# HDMI_RGB_LVDS_fertig_V5.net
KiCad netlist of a schematic drawn in EAGLE
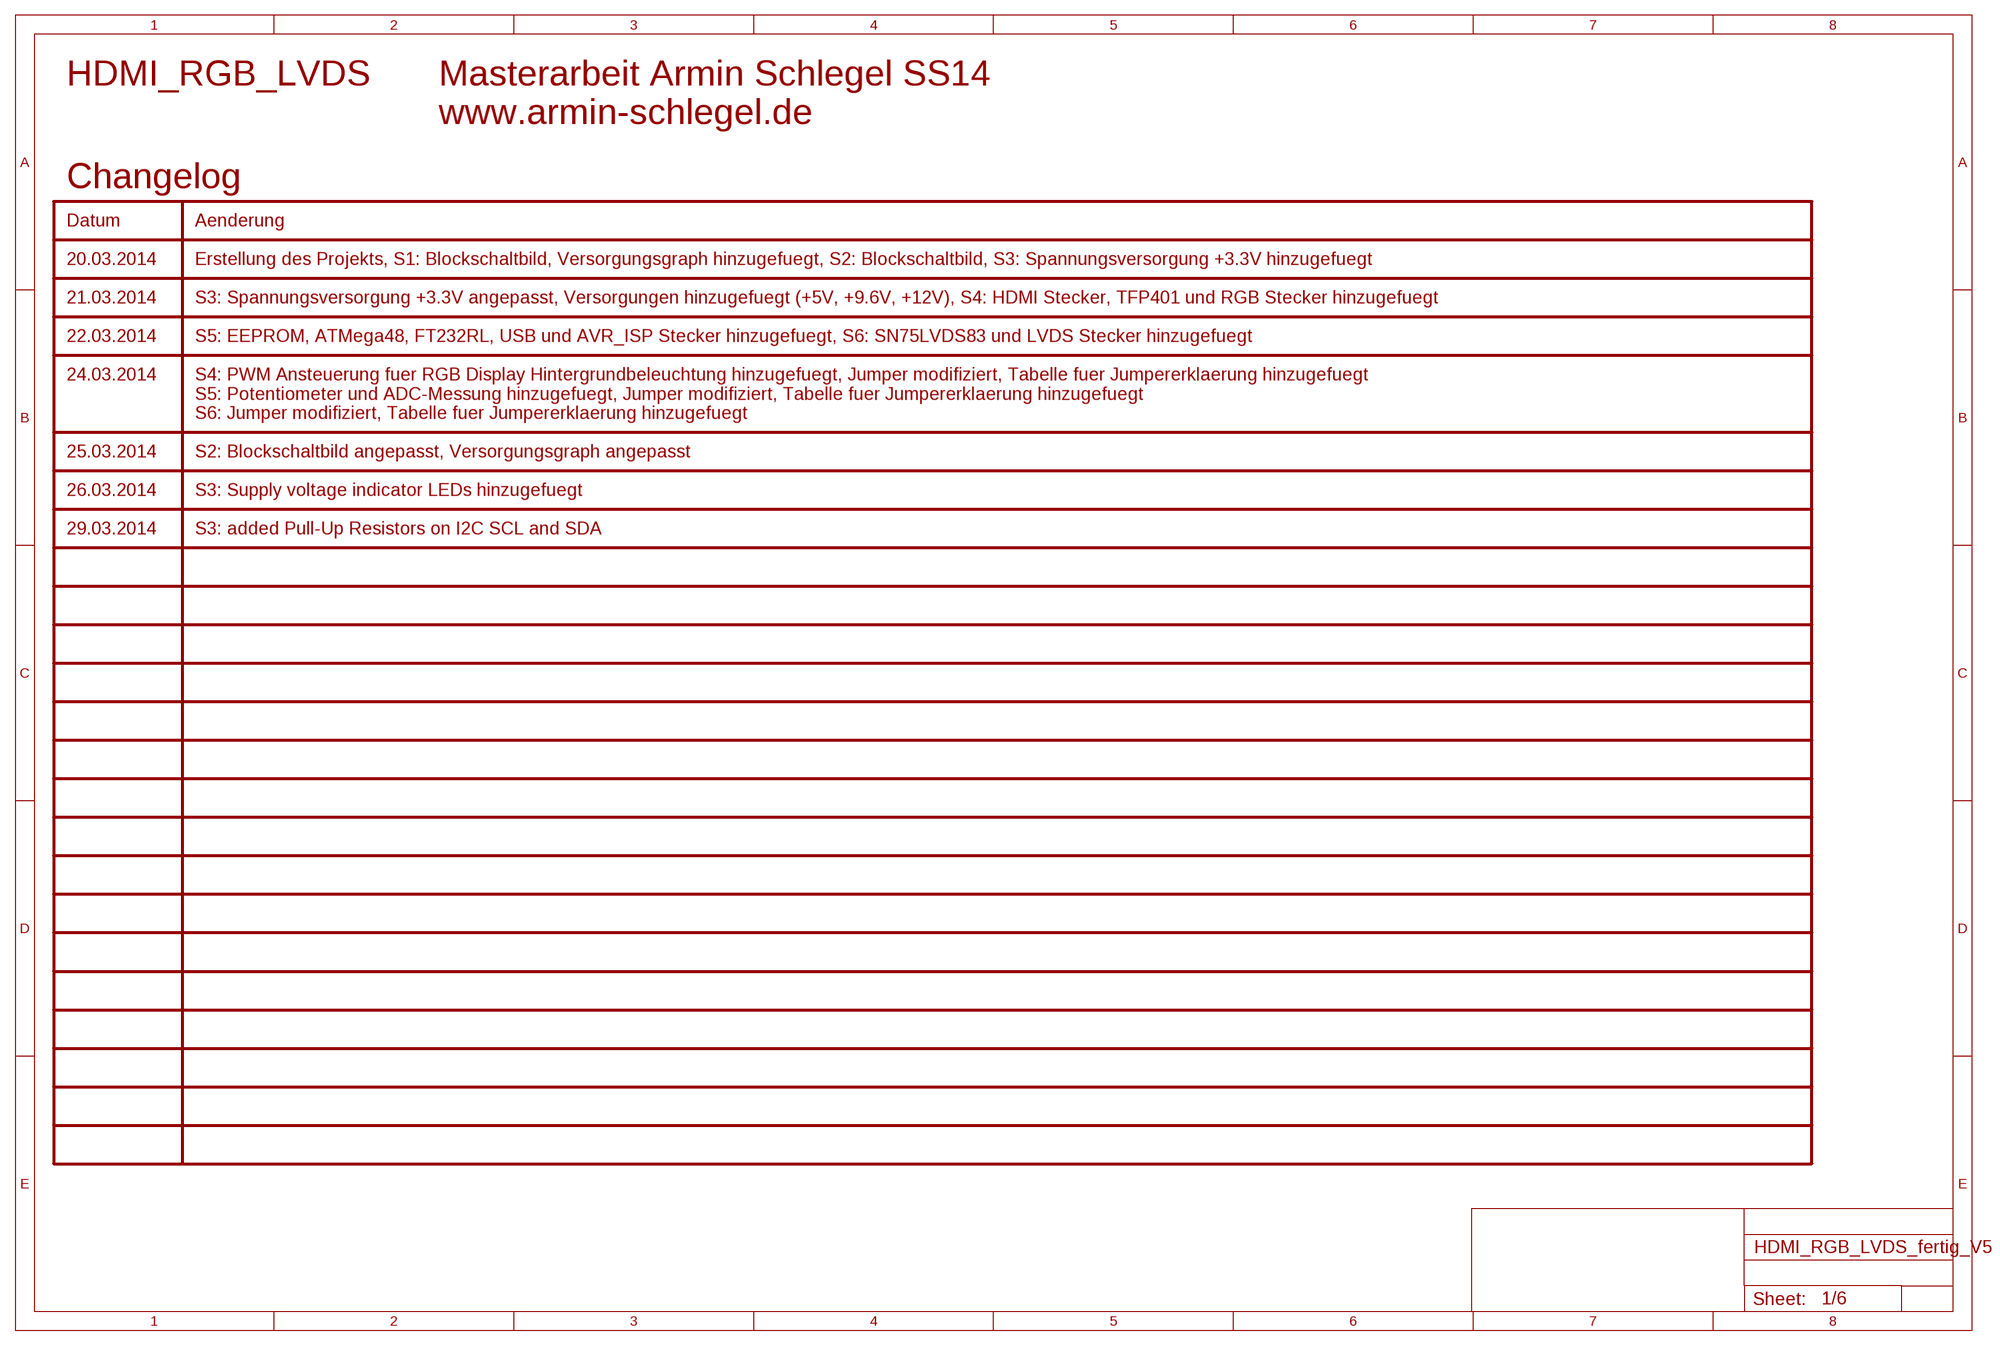
[diagram p0: schematic, sheet 1]
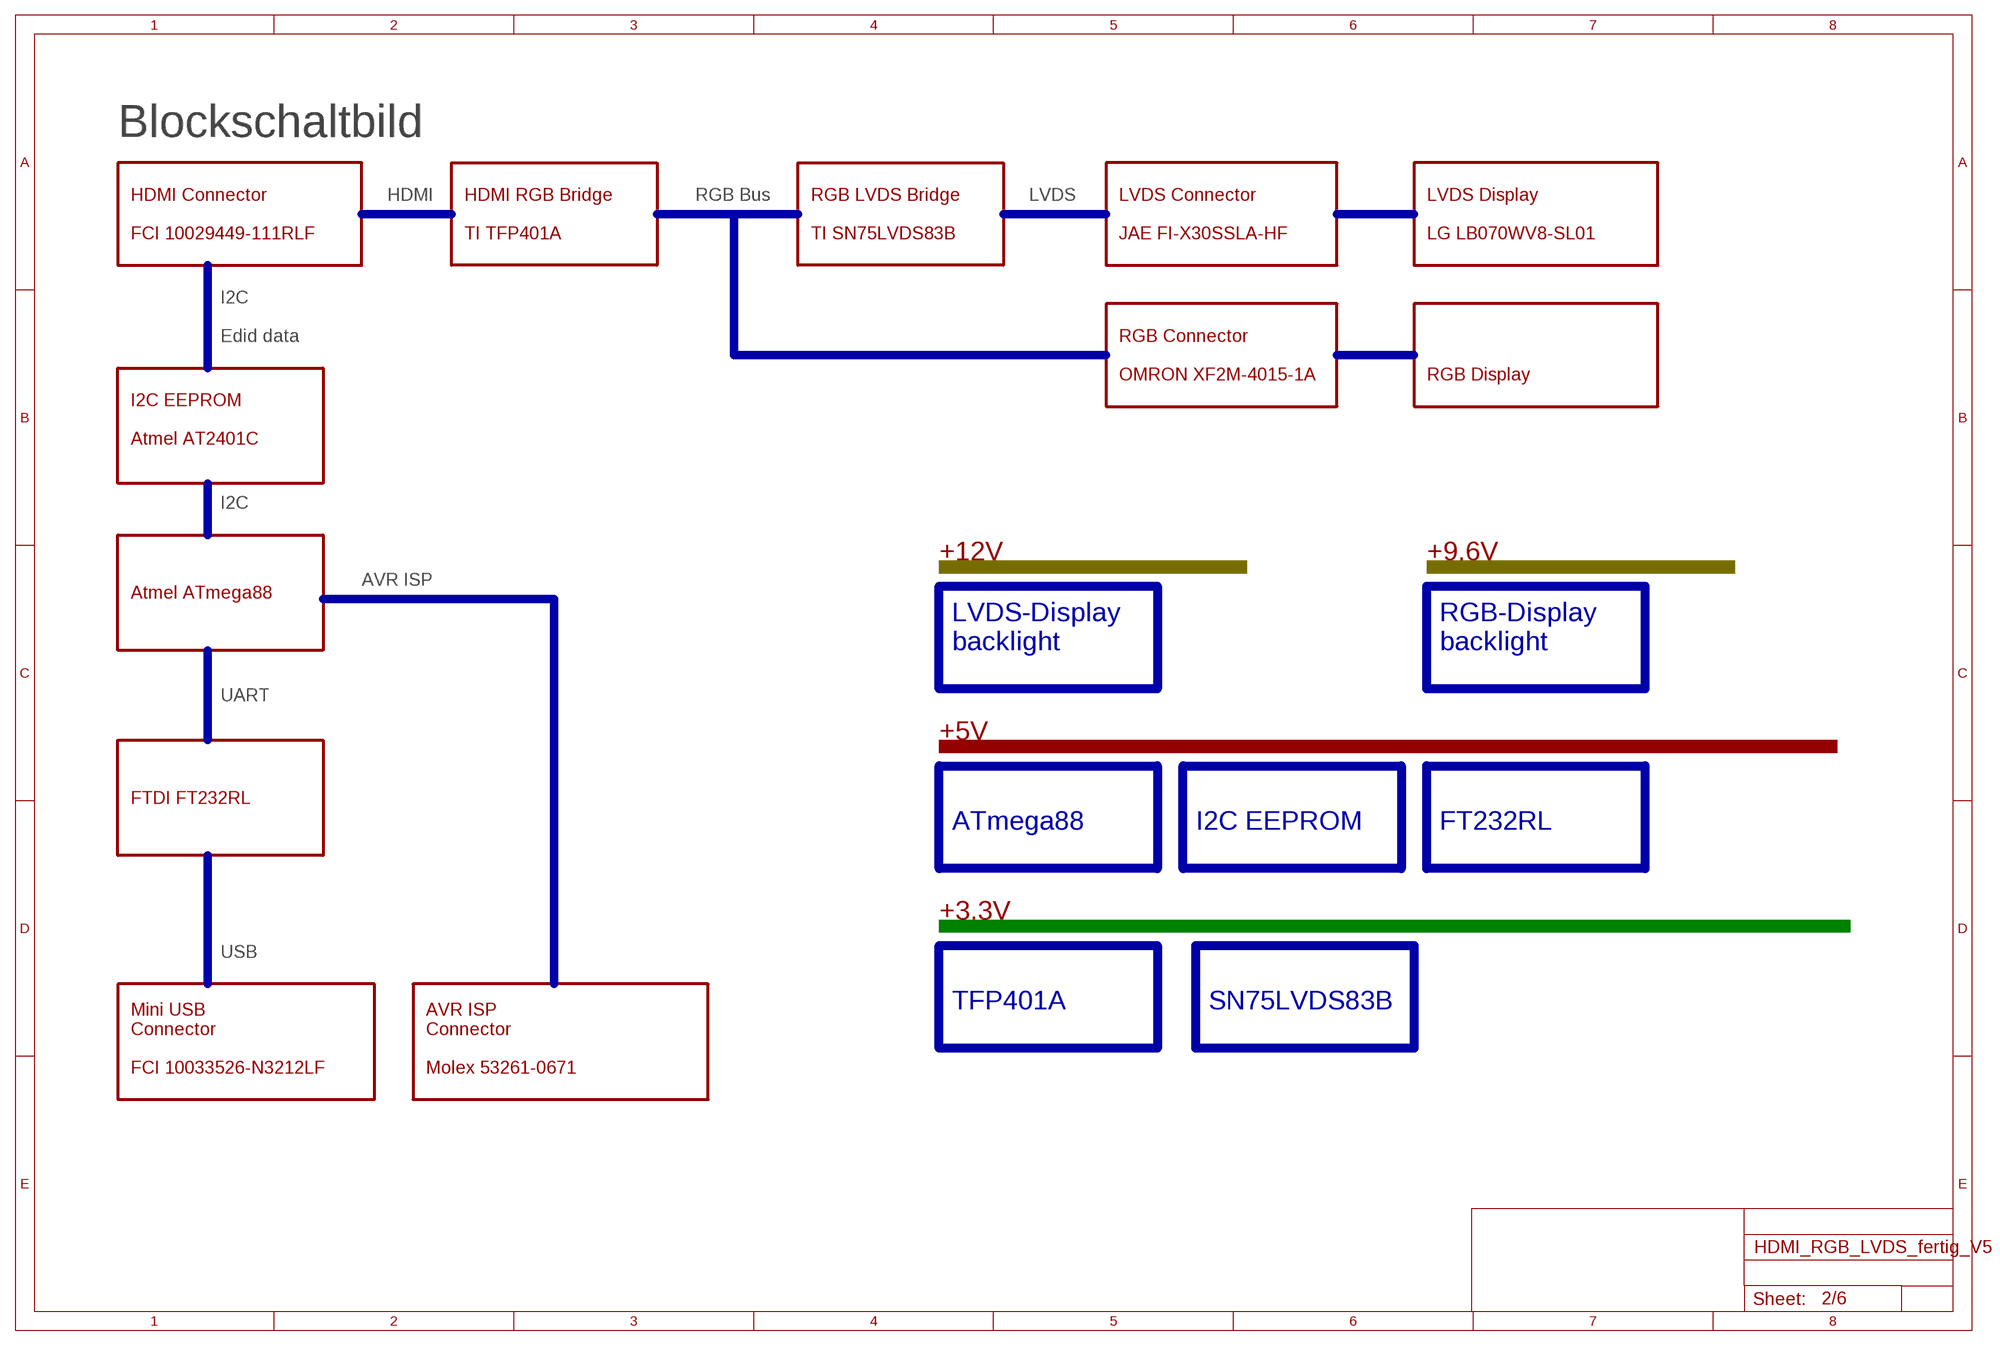
[diagram p1: schematic, sheet 2]
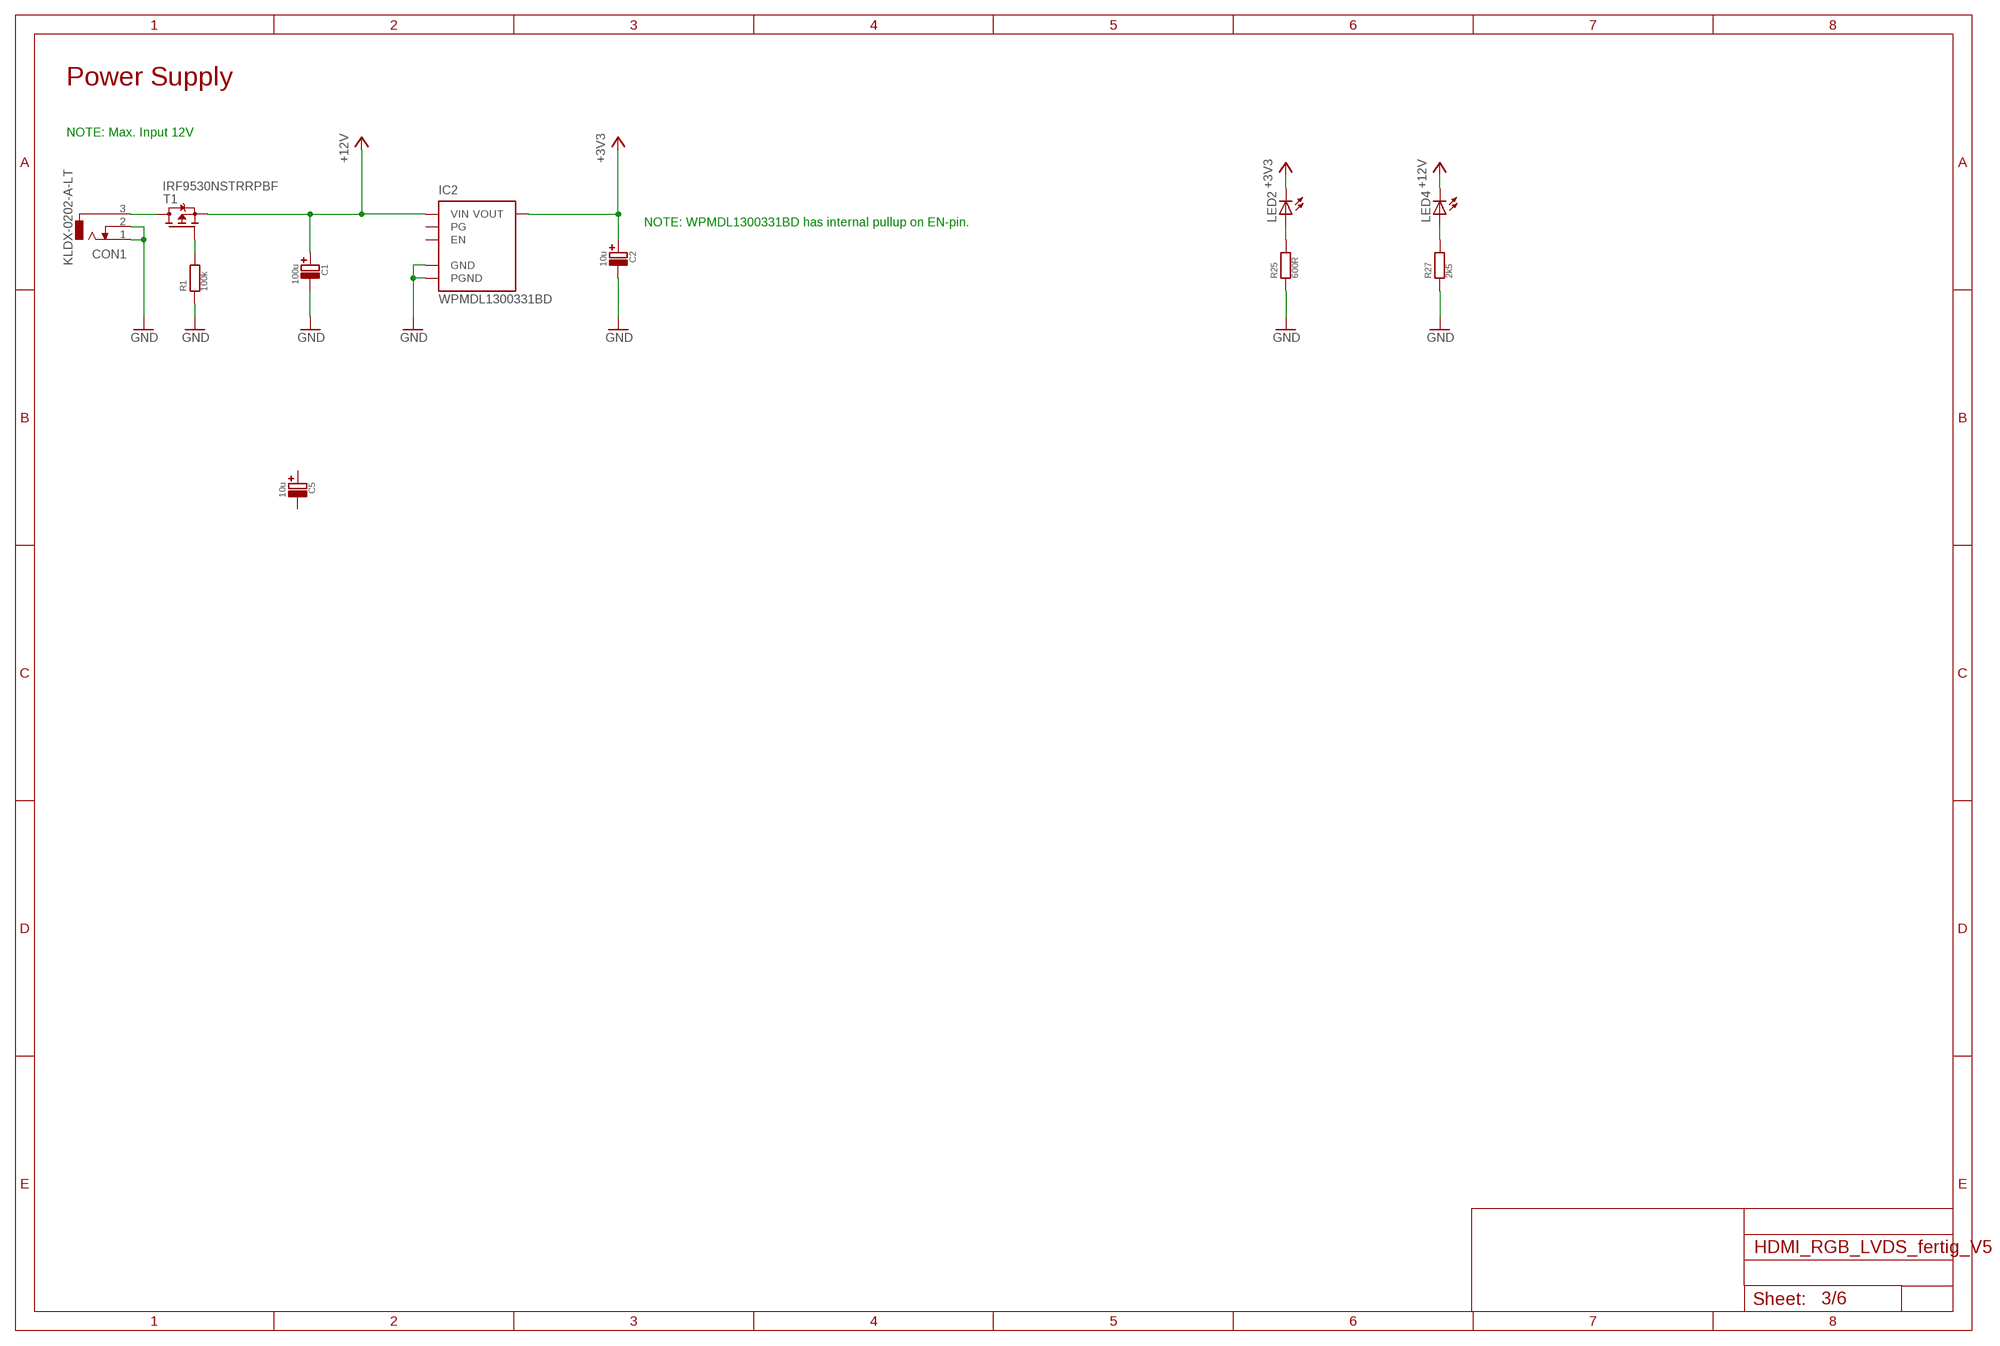
[diagram p2: schematic, sheet 3]
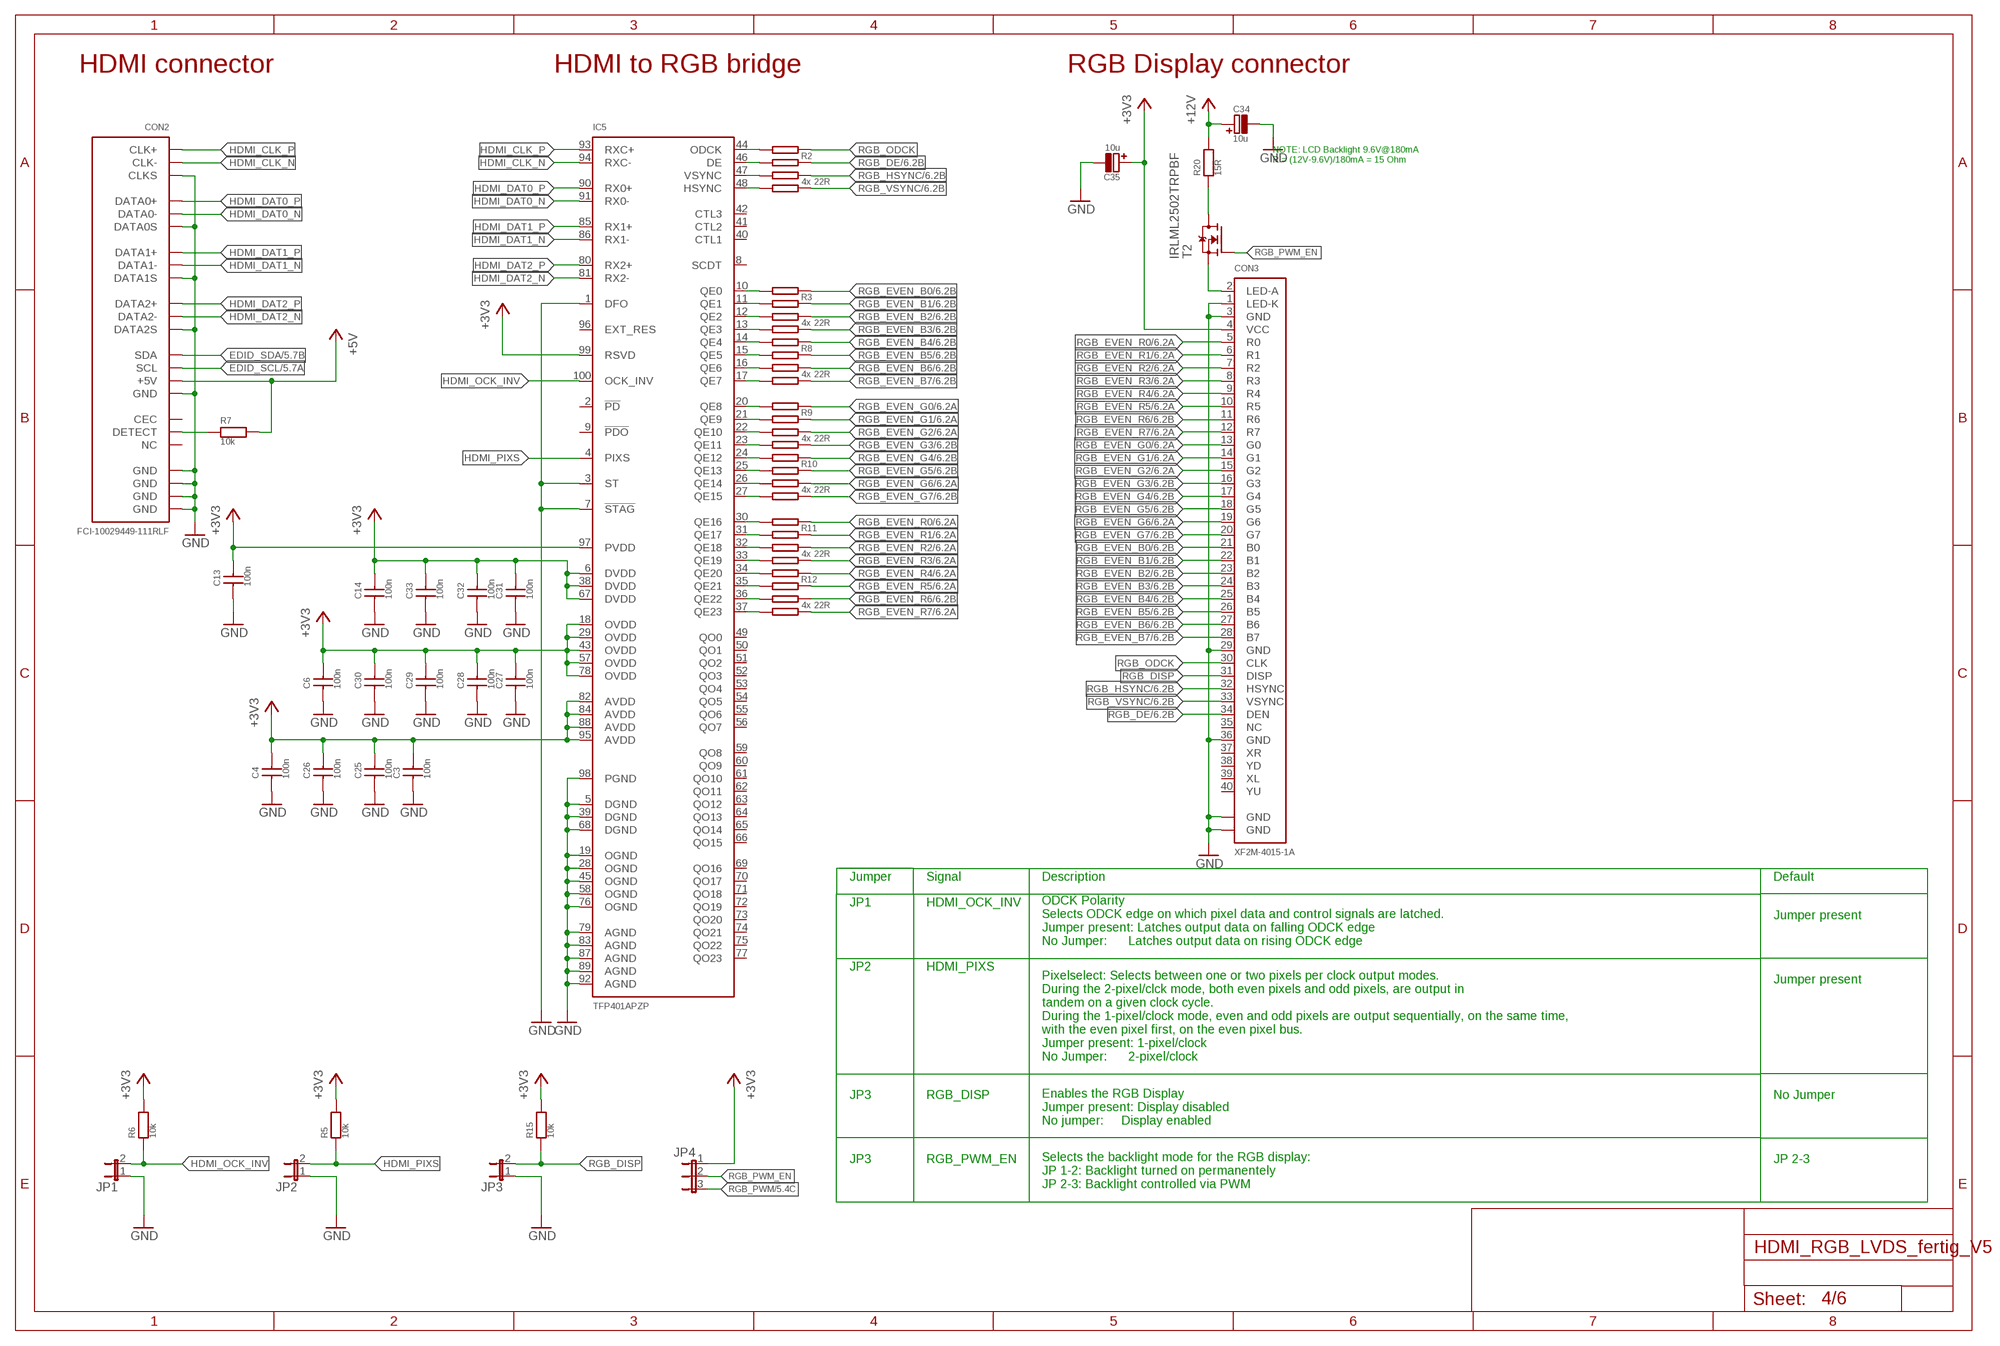
[diagram p3: schematic, sheet 4]
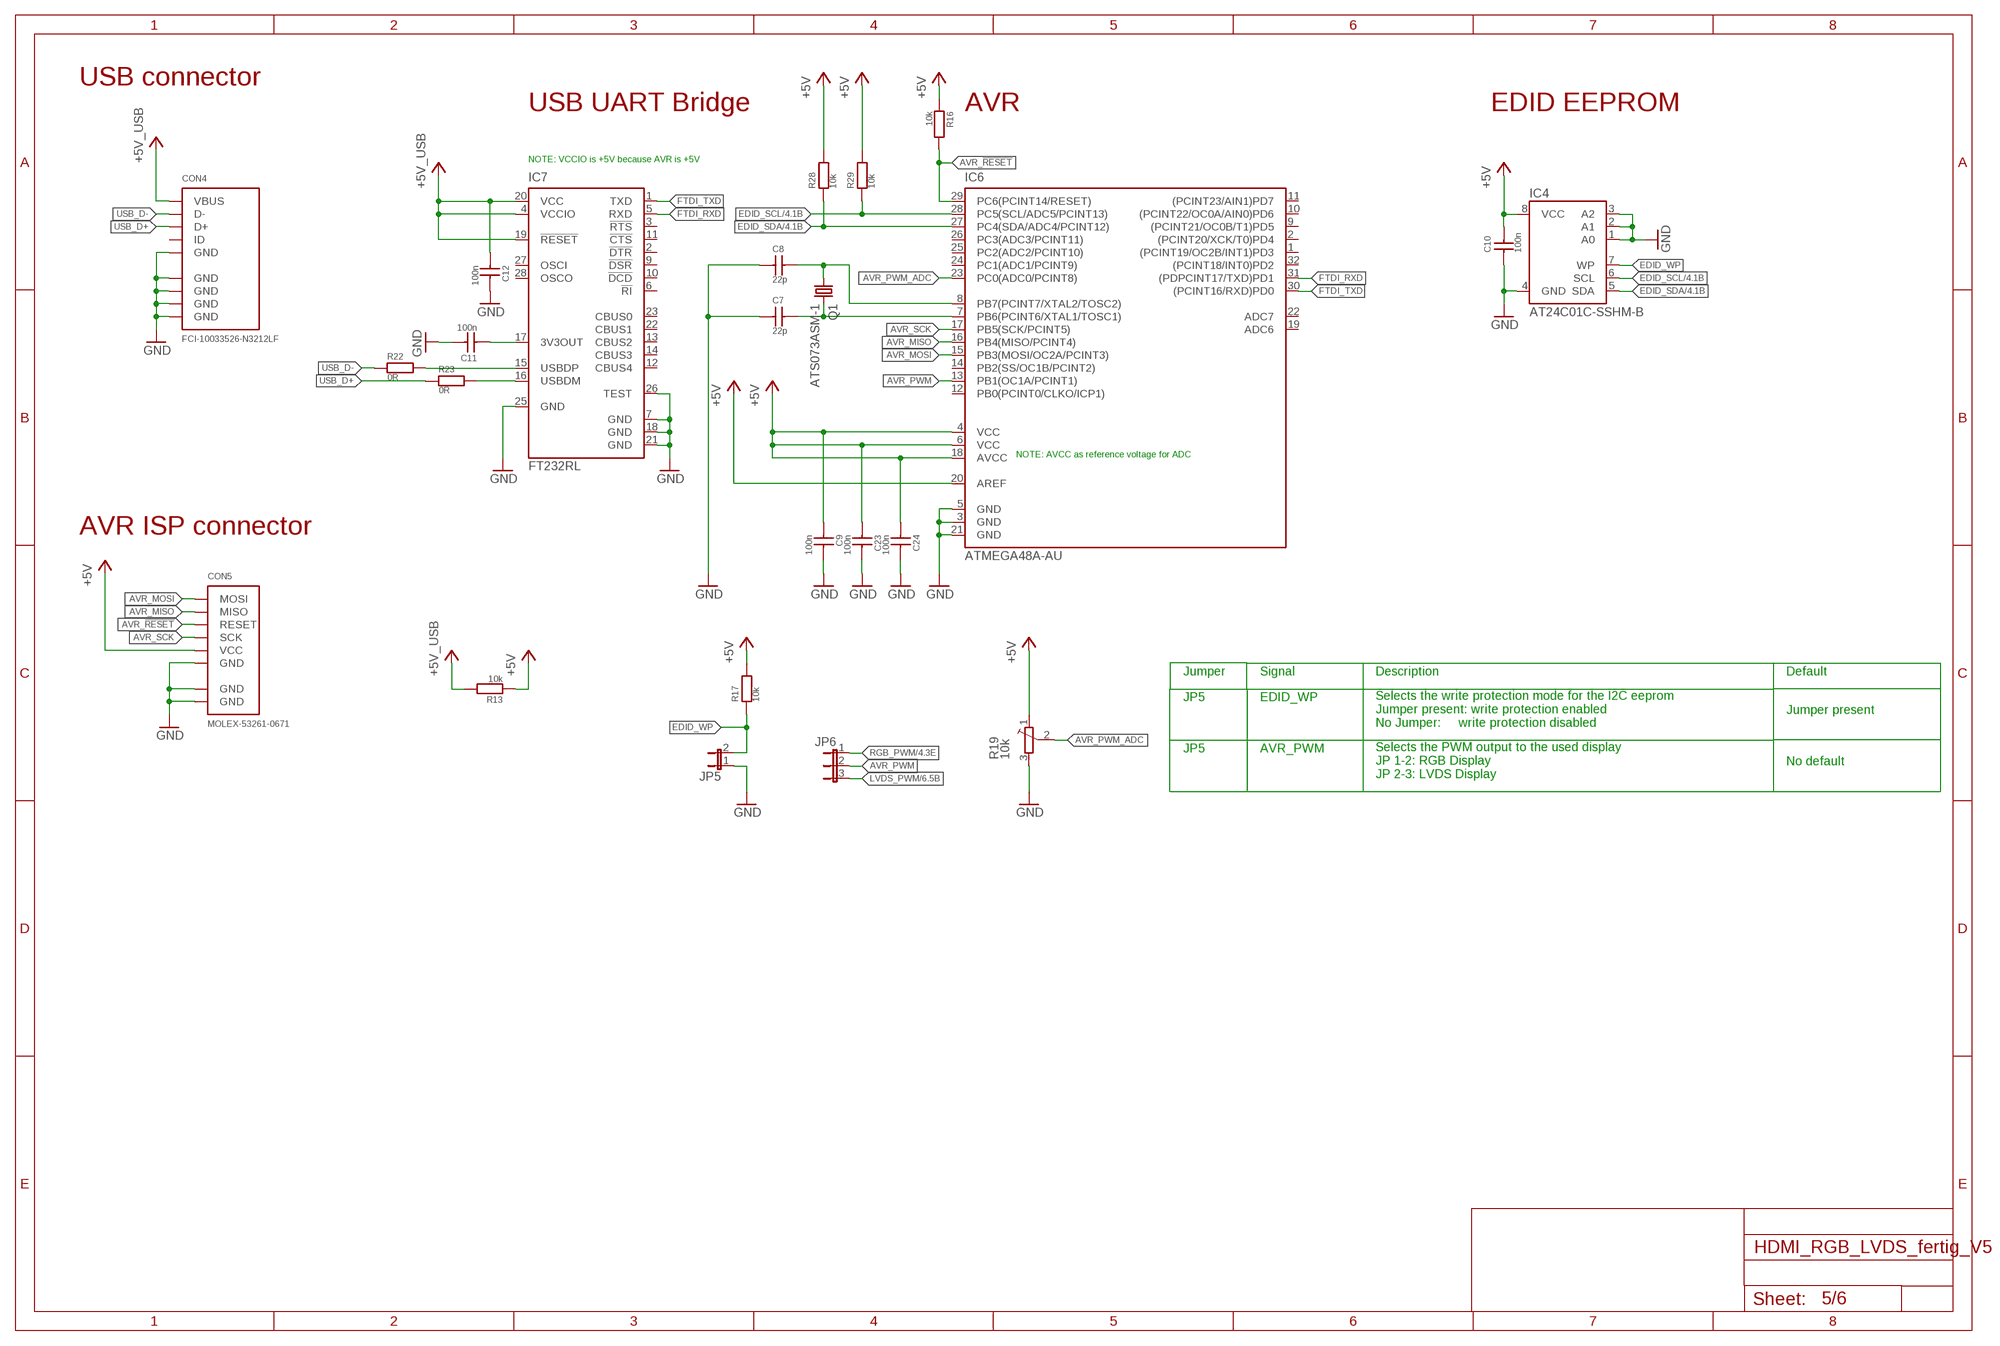
[diagram p4: schematic, sheet 5]
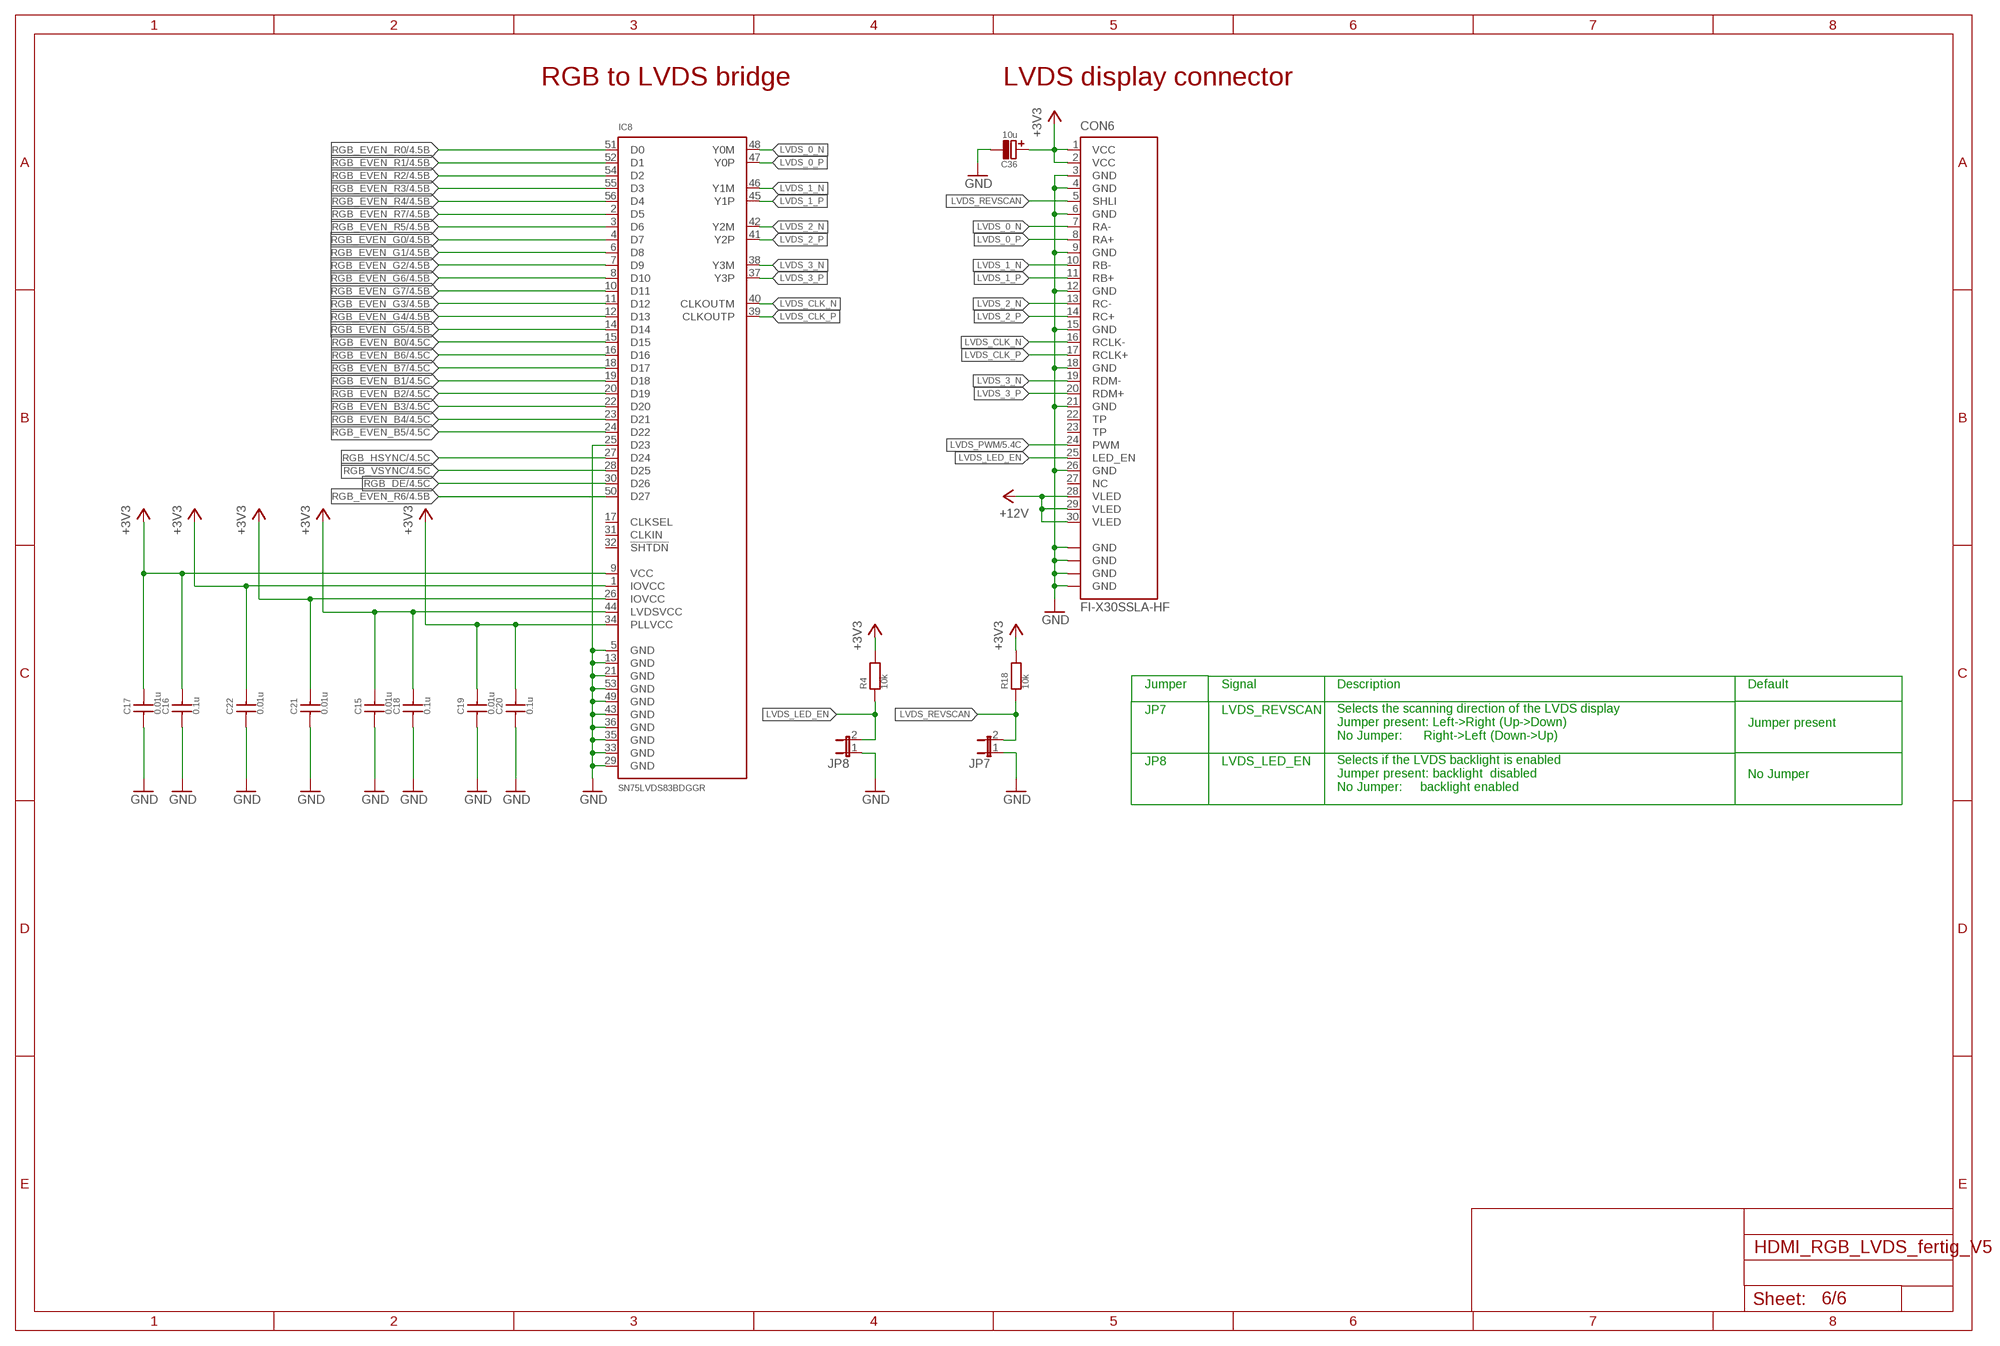
[diagram p5: schematic, sheet 6]

(export (version "E")
  (design (tool "Eeschema 10.0.6"))
  (components
    (comp (ref "C1")
      (value "100u")
      (footprint "eagle-import:C_POL_6X6MM")
      (libsource (lib "eagle-import") (part "RSS1C101MCN1GS"))
    )
    (comp (ref "C2")
      (value "10u")
      (footprint "eagle-import:C_POL_4X4MM")
      (libsource (lib "eagle-import") (part "C_POL4X4MM"))
    )
    (comp (ref "C5")
      (value "10u")
      (footprint "eagle-import:C_POL_4X4MM")
      (libsource (lib "eagle-import") (part "C_POL4X4MM"))
    )
    (comp (ref "CON1")
      (value "KLDX-0202-A-LT")
      (footprint "eagle-import:KLDX-0202-A-LT")
      (libsource (lib "eagle-import") (part "KLDX-0202-A-LT"))
    )
    (comp (ref "IC2")
      (value "WPMDL1300331BD")
      (footprint "eagle-import:TO263-5")
      (libsource (lib "eagle-import") (part "WPMDL1300331BD"))
    )
    (comp (ref "LED2")
      (value "LED0402")
      (footprint "eagle-import:LED0402")
      (libsource (lib "eagle-import") (part "LED0402"))
    )
    (comp (ref "LED4")
      (value "LED0402")
      (footprint "eagle-import:LED0402")
      (libsource (lib "eagle-import") (part "LED0402"))
    )
    (comp (ref "R1")
      (value "100k")
      (footprint "eagle-import:R0402")
      (libsource (lib "eagle-import") (part "R0402"))
    )
    (comp (ref "R25")
      (value "600R")
      (footprint "eagle-import:R0402")
      (libsource (lib "eagle-import") (part "R0402"))
    )
    (comp (ref "R27")
      (value "2k5")
      (footprint "eagle-import:R0402")
      (libsource (lib "eagle-import") (part "R0402"))
    )
    (comp (ref "T1")
      (value "IRF9530NSTRRPBF")
      (footprint "eagle-import:D2PAK")
      (libsource (lib "eagle-import") (part "IRF9530NSTRRPBF"))
    )
    (comp (ref "U$2")
      (value "FRAME_A3_LANDSCAPE")
      (footprint "eagle-import:FRAME")
      (libsource (lib "eagle-import") (part "FRAME_A3_LANDSCAPE"))
    )
    (comp (ref "C3")
      (value "100n")
      (footprint "eagle-import:C0402")
      (libsource (lib "eagle-import") (part "C_SMD0402"))
    )
    (comp (ref "C4")
      (value "100n")
      (footprint "eagle-import:C0402")
      (libsource (lib "eagle-import") (part "C_SMD0402"))
    )
    (comp (ref "C6")
      (value "100n")
      (footprint "eagle-import:C0402")
      (libsource (lib "eagle-import") (part "C_SMD0402"))
    )
    (comp (ref "C13")
      (value "100n")
      (footprint "eagle-import:C0402")
      (libsource (lib "eagle-import") (part "C_SMD0402"))
    )
    (comp (ref "C14")
      (value "100n")
      (footprint "eagle-import:C0402")
      (libsource (lib "eagle-import") (part "C_SMD0402"))
    )
    (comp (ref "C25")
      (value "100n")
      (footprint "eagle-import:C0402")
      (libsource (lib "eagle-import") (part "C_SMD0402"))
    )
    (comp (ref "C26")
      (value "100n")
      (footprint "eagle-import:C0402")
      (libsource (lib "eagle-import") (part "C_SMD0402"))
    )
    (comp (ref "C27")
      (value "100n")
      (footprint "eagle-import:C0402")
      (libsource (lib "eagle-import") (part "C_SMD0402"))
    )
    (comp (ref "C28")
      (value "100n")
      (footprint "eagle-import:C0402")
      (libsource (lib "eagle-import") (part "C_SMD0402"))
    )
    (comp (ref "C29")
      (value "100n")
      (footprint "eagle-import:C0402")
      (libsource (lib "eagle-import") (part "C_SMD0402"))
    )
    (comp (ref "C30")
      (value "100n")
      (footprint "eagle-import:C0402")
      (libsource (lib "eagle-import") (part "C_SMD0402"))
    )
    (comp (ref "C31")
      (value "100n")
      (footprint "eagle-import:C0402")
      (libsource (lib "eagle-import") (part "C_SMD0402"))
    )
    (comp (ref "C32")
      (value "100n")
      (footprint "eagle-import:C0402")
      (libsource (lib "eagle-import") (part "C_SMD0402"))
    )
    (comp (ref "C33")
      (value "100n")
      (footprint "eagle-import:C0402")
      (libsource (lib "eagle-import") (part "C_SMD0402"))
    )
    (comp (ref "C34")
      (value "10u")
      (footprint "eagle-import:C_POL_4X4MM")
      (libsource (lib "eagle-import") (part "C_POL4X4MM"))
    )
    (comp (ref "C35")
      (value "10u")
      (footprint "eagle-import:C_POL_4X4MM")
      (libsource (lib "eagle-import") (part "C_POL4X4MM"))
    )
    (comp (ref "CON2")
      (value "FCI-10029449-111RLF")
      (footprint "eagle-import:FCI-10029449-111RLF")
      (libsource (lib "eagle-import") (part "FCI-10029449-111RLF"))
    )
    (comp (ref "CON3")
      (value "XF2M-4015-1A")
      (footprint "eagle-import:XF2M-4015-1A")
      (libsource (lib "eagle-import") (part "XF2M-4015-1A"))
    )
    (comp (ref "IC5")
      (value "TFP401APZP")
      (footprint "eagle-import:HTQFP-100")
      (libsource (lib "eagle-import") (part "TFP401APZP"))
    )
    (comp (ref "JP1")
      (value "JUMPER2")
      (footprint "eagle-import:JUMPER2_THROUGHHOLE")
      (libsource (lib "eagle-import") (part "JUMPER2"))
    )
    (comp (ref "JP2")
      (value "JUMPER2")
      (footprint "eagle-import:JUMPER2_THROUGHHOLE")
      (libsource (lib "eagle-import") (part "JUMPER2"))
    )
    (comp (ref "JP3")
      (value "JUMPER2")
      (footprint "eagle-import:JUMPER2_THROUGHHOLE")
      (libsource (lib "eagle-import") (part "JUMPER2"))
    )
    (comp (ref "JP4")
      (value "JUMPER3")
      (footprint "eagle-import:JUMPER3_THROUGHHOLE")
      (libsource (lib "eagle-import") (part "JUMPER3"))
    )
    (comp (ref "R2")
      (value "22R")
      (footprint "eagle-import:R-ARRAY-4X0603")
      (libsource (lib "eagle-import") (part "CTR-742C083220JP-4X22R-4X0603"))
    )
    (comp (ref "R3")
      (value "22R")
      (footprint "eagle-import:R-ARRAY-4X0603")
      (libsource (lib "eagle-import") (part "CTR-742C083220JP-4X22R-4X0603"))
    )
    (comp (ref "R5")
      (value "10k")
      (footprint "eagle-import:R0402")
      (libsource (lib "eagle-import") (part "R0402"))
    )
    (comp (ref "R6")
      (value "10k")
      (footprint "eagle-import:R0402")
      (libsource (lib "eagle-import") (part "R0402"))
    )
    (comp (ref "R7")
      (value "10k")
      (footprint "eagle-import:R0402")
      (libsource (lib "eagle-import") (part "R0402"))
    )
    (comp (ref "R8")
      (value "22R")
      (footprint "eagle-import:R-ARRAY-4X0603")
      (libsource (lib "eagle-import") (part "CTR-742C083220JP-4X22R-4X0603"))
    )
    (comp (ref "R9")
      (value "22R")
      (footprint "eagle-import:R-ARRAY-4X0603")
      (libsource (lib "eagle-import") (part "CTR-742C083220JP-4X22R-4X0603"))
    )
    (comp (ref "R10")
      (value "22R")
      (footprint "eagle-import:R-ARRAY-4X0603")
      (libsource (lib "eagle-import") (part "CTR-742C083220JP-4X22R-4X0603"))
    )
    (comp (ref "R11")
      (value "22R")
      (footprint "eagle-import:R-ARRAY-4X0603")
      (libsource (lib "eagle-import") (part "CTR-742C083220JP-4X22R-4X0603"))
    )
    (comp (ref "R12")
      (value "22R")
      (footprint "eagle-import:R-ARRAY-4X0603")
      (libsource (lib "eagle-import") (part "CTR-742C083220JP-4X22R-4X0603"))
    )
    (comp (ref "R15")
      (value "10k")
      (footprint "eagle-import:R0402")
      (libsource (lib "eagle-import") (part "R0402"))
    )
    (comp (ref "R20")
      (value "15R")
      (footprint "eagle-import:R2512")
      (libsource (lib "eagle-import") (part "R2512"))
    )
    (comp (ref "T2")
      (value "IRLML2502TRPBF")
      (footprint "eagle-import:SOT23")
      (libsource (lib "eagle-import") (part "IRLML2502TRPBF"))
    )
    (comp (ref "U$3")
      (value "FRAME_A3_LANDSCAPE")
      (footprint "eagle-import:FRAME")
      (libsource (lib "eagle-import") (part "FRAME_A3_LANDSCAPE"))
    )
    (comp (ref "U$15")
      (value "FRAME_A3_LANDSCAPE")
      (footprint "eagle-import:FRAME")
      (libsource (lib "eagle-import") (part "FRAME_A3_LANDSCAPE"))
    )
    (comp (ref "C7")
      (value "22p")
      (footprint "eagle-import:C0402")
      (libsource (lib "eagle-import") (part "C_SMD0402"))
    )
    (comp (ref "C8")
      (value "22p")
      (footprint "eagle-import:C0402")
      (libsource (lib "eagle-import") (part "C_SMD0402"))
    )
    (comp (ref "C9")
      (value "100n")
      (footprint "eagle-import:C0402")
      (libsource (lib "eagle-import") (part "C_SMD0402"))
    )
    (comp (ref "C10")
      (value "100n")
      (footprint "eagle-import:C0402")
      (libsource (lib "eagle-import") (part "C_SMD0402"))
    )
    (comp (ref "C11")
      (value "100n")
      (footprint "eagle-import:C0402")
      (libsource (lib "eagle-import") (part "C_SMD0402"))
    )
    (comp (ref "C12")
      (value "100n")
      (footprint "eagle-import:C0402")
      (libsource (lib "eagle-import") (part "C_SMD0402"))
    )
    (comp (ref "C23")
      (value "100n")
      (footprint "eagle-import:C0402")
      (libsource (lib "eagle-import") (part "C_SMD0402"))
    )
    (comp (ref "C24")
      (value "100n")
      (footprint "eagle-import:C0402")
      (libsource (lib "eagle-import") (part "C_SMD0402"))
    )
    (comp (ref "CON4")
      (value "FCI-10033526-N3212LF")
      (footprint "eagle-import:FCI-10033526-N3212LF")
      (libsource (lib "eagle-import") (part "FCI-10033526-N3212LF"))
    )
    (comp (ref "CON5")
      (value "MOLEX-53261-0671")
      (footprint "eagle-import:MOLEX-53261-0671")
      (libsource (lib "eagle-import") (part "MOLEX-53261-0671"))
    )
    (comp (ref "IC4")
      (value "AT24C01C-SSHM-B")
      (footprint "eagle-import:SOIC8")
      (libsource (lib "eagle-import") (part "AT24C01C-SSHM-B"))
    )
    (comp (ref "IC6")
      (value "ATMEGA48A-AU")
      (footprint "eagle-import:TQFP32")
      (libsource (lib "eagle-import") (part "ATMEGA48A-AU"))
    )
    (comp (ref "IC7")
      (value "FT232RL")
      (footprint "eagle-import:SSOP28")
      (libsource (lib "eagle-import") (part "FT232RL"))
    )
    (comp (ref "JP5")
      (value "JUMPER2")
      (footprint "eagle-import:JUMPER2_THROUGHHOLE")
      (libsource (lib "eagle-import") (part "JUMPER2"))
    )
    (comp (ref "JP6")
      (value "JUMPER3")
      (footprint "eagle-import:JUMPER3_THROUGHHOLE")
      (libsource (lib "eagle-import") (part "JUMPER3"))
    )
    (comp (ref "Q1")
      (value "ATS073ASM-1")
      (footprint "eagle-import:HC49_USSM")
      (libsource (lib "eagle-import") (part "ATS073ASM-1"))
    )
    (comp (ref "R13")
      (value "10k")
      (footprint "eagle-import:R0402")
      (libsource (lib "eagle-import") (part "R0402"))
    )
    (comp (ref "R16")
      (value "10k")
      (footprint "eagle-import:R0402")
      (libsource (lib "eagle-import") (part "R0402"))
    )
    (comp (ref "R17")
      (value "10k")
      (footprint "eagle-import:R0402")
      (libsource (lib "eagle-import") (part "R0402"))
    )
    (comp (ref "R19")
      (value "10k")
      (footprint "eagle-import:35WR5KLFTR")
      (libsource (lib "eagle-import") (part "35WR5KLFTR"))
    )
    (comp (ref "R22")
      (value "0R")
      (footprint "eagle-import:R0402")
      (libsource (lib "eagle-import") (part "R0402"))
    )
    (comp (ref "R23")
      (value "0R")
      (footprint "eagle-import:R0402")
      (libsource (lib "eagle-import") (part "R0402"))
    )
    (comp (ref "R28")
      (value "10k")
      (footprint "eagle-import:R0402")
      (libsource (lib "eagle-import") (part "R0402"))
    )
    (comp (ref "R29")
      (value "10k")
      (footprint "eagle-import:R0402")
      (libsource (lib "eagle-import") (part "R0402"))
    )
    (comp (ref "U$4")
      (value "FRAME_A3_LANDSCAPE")
      (footprint "eagle-import:FRAME")
      (libsource (lib "eagle-import") (part "FRAME_A3_LANDSCAPE"))
    )
    (comp (ref "C15")
      (value "0.01u")
      (footprint "eagle-import:C0402")
      (libsource (lib "eagle-import") (part "C_SMD0402"))
    )
    (comp (ref "C16")
      (value "0.1u")
      (footprint "eagle-import:C0402")
      (libsource (lib "eagle-import") (part "C_SMD0402"))
    )
    (comp (ref "C17")
      (value "0.01u")
      (footprint "eagle-import:C0402")
      (libsource (lib "eagle-import") (part "C_SMD0402"))
    )
    (comp (ref "C18")
      (value "0.1u")
      (footprint "eagle-import:C0402")
      (libsource (lib "eagle-import") (part "C_SMD0402"))
    )
    (comp (ref "C19")
      (value "0.01u")
      (footprint "eagle-import:C0402")
      (libsource (lib "eagle-import") (part "C_SMD0402"))
    )
    (comp (ref "C20")
      (value "0.1u")
      (footprint "eagle-import:C0402")
      (libsource (lib "eagle-import") (part "C_SMD0402"))
    )
    (comp (ref "C21")
      (value "0.01u")
      (footprint "eagle-import:C0402")
      (libsource (lib "eagle-import") (part "C_SMD0402"))
    )
    (comp (ref "C22")
      (value "0.01u")
      (footprint "eagle-import:C0402")
      (libsource (lib "eagle-import") (part "C_SMD0402"))
    )
    (comp (ref "C36")
      (value "10u")
      (footprint "eagle-import:C_POL_4X4MM")
      (libsource (lib "eagle-import") (part "C_POL4X4MM"))
    )
    (comp (ref "CON6")
      (value "FI-X30SSLA-HF")
      (footprint "eagle-import:FI-X30SSLA-HF")
      (libsource (lib "eagle-import") (part "FI-X30SSLA-HF"))
    )
    (comp (ref "IC8")
      (value "SN75LVDS83BDGGR")
      (footprint "eagle-import:TSSOP-56")
      (libsource (lib "eagle-import") (part "SN75LVDS83BDGGR"))
    )
    (comp (ref "JP7")
      (value "JUMPER2")
      (footprint "eagle-import:JUMPER2_THROUGHHOLE")
      (libsource (lib "eagle-import") (part "JUMPER2"))
    )
    (comp (ref "JP8")
      (value "JUMPER2")
      (footprint "eagle-import:JUMPER2_THROUGHHOLE")
      (libsource (lib "eagle-import") (part "JUMPER2"))
    )
    (comp (ref "R4")
      (value "10k")
      (footprint "eagle-import:R0402")
      (libsource (lib "eagle-import") (part "R0402"))
    )
    (comp (ref "R18")
      (value "10k")
      (footprint "eagle-import:R0402")
      (libsource (lib "eagle-import") (part "R0402"))
    )
    (comp (ref "U$5")
      (value "FRAME_A3_LANDSCAPE")
      (footprint "eagle-import:FRAME")
      (libsource (lib "eagle-import") (part "FRAME_A3_LANDSCAPE"))
    )
    (comp (ref "U$1")
      (value "FRAME_A3_LANDSCAPE")
      (footprint "eagle-import:FRAME")
      (libsource (lib "eagle-import") (part "FRAME_A3_LANDSCAPE"))
    )
  )
  (nets
    (net (code "3") (name "+3V3") (class "Default")
      (node (ref "C13") (pin "2") (pinfunction "P$2_2") (pintype "passive"))
      (node (ref "C14") (pin "2") (pinfunction "P$2_2") (pintype "passive"))
      (node (ref "C15") (pin "2") (pinfunction "P$2_2") (pintype "passive"))
      (node (ref "C16") (pin "2") (pinfunction "P$2_2") (pintype "passive"))
      (node (ref "C17") (pin "2") (pinfunction "P$2_2") (pintype "passive"))
      (node (ref "C18") (pin "2") (pinfunction "P$2_2") (pintype "passive"))
      (node (ref "C19") (pin "2") (pinfunction "P$2_2") (pintype "passive"))
      (node (ref "C2") (pin "+") (pinfunction "+_+") (pintype "passive"))
      (node (ref "C20") (pin "2") (pinfunction "P$2_2") (pintype "passive"))
      (node (ref "C21") (pin "2") (pinfunction "P$2_2") (pintype "passive"))
      (node (ref "C22") (pin "2") (pinfunction "P$2_2") (pintype "passive"))
      (node (ref "C25") (pin "2") (pinfunction "P$2_2") (pintype "passive"))
      (node (ref "C26") (pin "2") (pinfunction "P$2_2") (pintype "passive"))
      (node (ref "C27") (pin "2") (pinfunction "P$2_2") (pintype "passive"))
      (node (ref "C28") (pin "2") (pinfunction "P$2_2") (pintype "passive"))
      (node (ref "C29") (pin "2") (pinfunction "P$2_2") (pintype "passive"))
      (node (ref "C3") (pin "2") (pinfunction "P$2_2") (pintype "passive"))
      (node (ref "C30") (pin "2") (pinfunction "P$2_2") (pintype "passive"))
      (node (ref "C31") (pin "2") (pinfunction "P$2_2") (pintype "passive"))
      (node (ref "C32") (pin "2") (pinfunction "P$2_2") (pintype "passive"))
      (node (ref "C33") (pin "2") (pinfunction "P$2_2") (pintype "passive"))
      (node (ref "C35") (pin "+") (pinfunction "+_+") (pintype "passive"))
      (node (ref "C36") (pin "+") (pinfunction "+_+") (pintype "passive"))
      (node (ref "C4") (pin "2") (pinfunction "P$2_2") (pintype "passive"))
      (node (ref "C6") (pin "2") (pinfunction "P$2_2") (pintype "passive"))
      (node (ref "CON3") (pin "4") (pinfunction "VCC_4") (pintype "bidirectional"))
      (node (ref "CON6") (pin "1") (pinfunction "VCC_1") (pintype "bidirectional"))
      (node (ref "CON6") (pin "2") (pinfunction "VCC_2") (pintype "bidirectional"))
      (node (ref "IC2") (pin "3") (pinfunction "VOUT_3") (pintype "bidirectional"))
      (node (ref "IC5") (pin "18") (pinfunction "OVDD_18") (pintype "power_in"))
      (node (ref "IC5") (pin "29") (pinfunction "OVDD_29") (pintype "power_in"))
      (node (ref "IC5") (pin "38") (pinfunction "DVDD_38") (pintype "power_in"))
      (node (ref "IC5") (pin "43") (pinfunction "OVDD_43") (pintype "power_in"))
      (node (ref "IC5") (pin "57") (pinfunction "OVDD_57") (pintype "power_in"))
      (node (ref "IC5") (pin "6") (pinfunction "DVDD_6") (pintype "power_in"))
      (node (ref "IC5") (pin "67") (pinfunction "DVDD_67") (pintype "power_in"))
      (node (ref "IC5") (pin "78") (pinfunction "OVDD_78") (pintype "power_in"))
      (node (ref "IC5") (pin "82") (pinfunction "AVDD_82") (pintype "power_in"))
      (node (ref "IC5") (pin "84") (pinfunction "AVDD_84") (pintype "power_in"))
      (node (ref "IC5") (pin "88") (pinfunction "AVDD_88") (pintype "power_in"))
      (node (ref "IC5") (pin "95") (pinfunction "AVDD_95") (pintype "power_in"))
      (node (ref "IC5") (pin "97") (pinfunction "PVDD_97") (pintype "power_in"))
      (node (ref "IC5") (pin "99") (pinfunction "RSVD_99") (pintype "bidirectional"))
      (node (ref "IC8") (pin "1") (pinfunction "IOVCC_1") (pintype "power_in"))
      (node (ref "IC8") (pin "26") (pinfunction "IOVCC_26") (pintype "power_in"))
      (node (ref "IC8") (pin "34") (pinfunction "PLLVCC_34") (pintype "power_in"))
      (node (ref "IC8") (pin "44") (pinfunction "LVDSVCC_44") (pintype "power_in"))
      (node (ref "IC8") (pin "9") (pinfunction "VCC_9") (pintype "power_in"))
      (node (ref "JP4") (pin "1") (pinfunction "1_1") (pintype "passive"))
      (node (ref "LED2") (pin "C") (pinfunction "C_C") (pintype "passive"))
      (node (ref "R15") (pin "2") (pinfunction "P$2_2") (pintype "passive"))
      (node (ref "R18") (pin "2") (pinfunction "P$2_2") (pintype "passive"))
      (node (ref "R4") (pin "2") (pinfunction "P$2_2") (pintype "passive"))
      (node (ref "R5") (pin "2") (pinfunction "P$2_2") (pintype "passive"))
      (node (ref "R6") (pin "2") (pinfunction "P$2_2") (pintype "passive"))
    )
    (net (code "4") (name "+5V") (class "Default")
      (node (ref "C10") (pin "2") (pinfunction "P$2_2") (pintype "passive"))
      (node (ref "C23") (pin "1") (pinfunction "P$1_1") (pintype "passive"))
      (node (ref "C24") (pin "1") (pinfunction "P$1_1") (pintype "passive"))
      (node (ref "C9") (pin "1") (pinfunction "P$1_1") (pintype "passive"))
      (node (ref "CON2") (pin "18") (pinfunction "+5V_18") (pintype "bidirectional"))
      (node (ref "CON5") (pin "5") (pinfunction "VCC_5") (pintype "bidirectional"))
      (node (ref "IC4") (pin "8") (pinfunction "VCC_8") (pintype "power_in"))
      (node (ref "IC6") (pin "18") (pinfunction "AVCC_18") (pintype "power_in"))
      (node (ref "IC6") (pin "20") (pinfunction "AREF_20") (pintype "power_in"))
      (node (ref "IC6") (pin "4") (pinfunction "VCC_4") (pintype "power_in"))
      (node (ref "IC6") (pin "6") (pinfunction "VCC_6") (pintype "power_in"))
      (node (ref "R13") (pin "1") (pinfunction "P$1_1") (pintype "passive"))
      (node (ref "R16") (pin "1") (pinfunction "P$1_1") (pintype "passive"))
      (node (ref "R17") (pin "2") (pinfunction "P$2_2") (pintype "passive"))
      (node (ref "R19") (pin "1") (pinfunction "E_1") (pintype "passive"))
      (node (ref "R28") (pin "2") (pinfunction "P$2_2") (pintype "passive"))
      (node (ref "R29") (pin "2") (pinfunction "P$2_2") (pintype "passive"))
      (node (ref "R7") (pin "2") (pinfunction "P$2_2") (pintype "passive"))
    )
    (net (code "5") (name "+5V_USB") (class "Default")
      (node (ref "C12") (pin "1") (pinfunction "P$1_1") (pintype "passive"))
      (node (ref "CON4") (pin "1") (pinfunction "VBUS_1") (pintype "bidirectional"))
      (node (ref "IC7") (pin "19") (pinfunction "~{RESET}_19") (pintype "input"))
      (node (ref "IC7") (pin "20") (pinfunction "VCC_20") (pintype "power_in"))
      (node (ref "IC7") (pin "4") (pinfunction "VCCIO_4") (pintype "power_in"))
      (node (ref "R13") (pin "2") (pinfunction "P$2_2") (pintype "passive"))
    )
    (net (code "6") (name "+12V") (class "Default")
      (node (ref "C1") (pin "+") (pinfunction "+_+") (pintype "passive"))
      (node (ref "C34") (pin "+") (pinfunction "+_+") (pintype "passive"))
      (node (ref "CON6") (pin "28") (pinfunction "VLED_28") (pintype "bidirectional"))
      (node (ref "CON6") (pin "29") (pinfunction "VLED_29") (pintype "bidirectional"))
      (node (ref "CON6") (pin "30") (pinfunction "VLED_30") (pintype "bidirectional"))
      (node (ref "IC2") (pin "1") (pinfunction "VIN_1") (pintype "bidirectional"))
      (node (ref "LED4") (pin "C") (pinfunction "C_C") (pintype "passive"))
      (node (ref "R20") (pin "2") (pinfunction "P$2_2") (pintype "passive"))
      (node (ref "T1") (pin "3") (pinfunction "S_3") (pintype "passive"))
    )
    (net (code "9") (name "AVR_MISO") (class "Default")
      (node (ref "CON5") (pin "2") (pinfunction "MISO_2") (pintype "bidirectional"))
      (node (ref "IC6") (pin "16") (pinfunction "PB4(MISO/PCINT4)_16") (pintype "bidirectional"))
    )
    (net (code "10") (name "AVR_MOSI") (class "Default")
      (node (ref "CON5") (pin "1") (pinfunction "MOSI_1") (pintype "bidirectional"))
      (node (ref "IC6") (pin "15") (pinfunction "PB3(MOSI/OC2A/PCINT3)_15") (pintype "bidirectional"))
    )
    (net (code "11") (name "AVR_PWM") (class "Default")
      (node (ref "IC6") (pin "13") (pinfunction "PB1(OC1A/PCINT1)_13") (pintype "bidirectional"))
      (node (ref "JP6") (pin "2") (pinfunction "2_2") (pintype "passive"))
    )
    (net (code "12") (name "AVR_PWM_ADC") (class "Default")
      (node (ref "IC6") (pin "23") (pinfunction "PC0(ADC0/PCINT8)_23") (pintype "bidirectional"))
      (node (ref "R19") (pin "2") (pinfunction "S_2") (pintype "passive"))
    )
    (net (code "13") (name "AVR_SCK") (class "Default")
      (node (ref "CON5") (pin "4") (pinfunction "SCK_4") (pintype "bidirectional"))
      (node (ref "IC6") (pin "17") (pinfunction "PB5(SCK/PCINT5)_17") (pintype "bidirectional"))
    )
    (net (code "14") (name "AVR_~{RESET}") (class "Default")
      (node (ref "CON5") (pin "3") (pinfunction "RESET_3") (pintype "bidirectional"))
      (node (ref "IC6") (pin "29") (pinfunction "PC6(PCINT14/RESET)_29") (pintype "bidirectional"))
      (node (ref "R16") (pin "2") (pinfunction "P$2_2") (pintype "passive"))
    )
    (net (code "15") (name "EDID_SCL") (class "Default")
      (node (ref "CON2") (pin "15") (pinfunction "SCL_15") (pintype "bidirectional"))
      (node (ref "IC4") (pin "6") (pinfunction "SCL_6") (pintype "bidirectional"))
      (node (ref "IC6") (pin "28") (pinfunction "PC5(SCL/ADC5/PCINT13)_28") (pintype "bidirectional"))
      (node (ref "R29") (pin "1") (pinfunction "P$1_1") (pintype "passive"))
    )
    (net (code "16") (name "EDID_SDA") (class "Default")
      (node (ref "CON2") (pin "16") (pinfunction "SDA_16") (pintype "bidirectional"))
      (node (ref "IC4") (pin "5") (pinfunction "SDA_5") (pintype "bidirectional"))
      (node (ref "IC6") (pin "27") (pinfunction "PC4(SDA/ADC4/PCINT12)_27") (pintype "bidirectional"))
      (node (ref "R28") (pin "1") (pinfunction "P$1_1") (pintype "passive"))
    )
    (net (code "17") (name "EDID_WP") (class "Default")
      (node (ref "IC4") (pin "7") (pinfunction "WP_7") (pintype "input"))
      (node (ref "JP5") (pin "2") (pinfunction "2_2") (pintype "passive"))
      (node (ref "R17") (pin "1") (pinfunction "P$1_1") (pintype "passive"))
    )
    (net (code "18") (name "FTDI_RXD") (class "Default")
      (node (ref "IC6") (pin "31") (pinfunction "(PDPCINT17/TXD)PD1_31") (pintype "bidirectional"))
      (node (ref "IC7") (pin "5") (pinfunction "RXD_5") (pintype "input"))
    )
    (net (code "19") (name "FTDI_TXD") (class "Default")
      (node (ref "IC6") (pin "30") (pinfunction "(PCINT16/RXD)PD0_30") (pintype "bidirectional"))
      (node (ref "IC7") (pin "1") (pinfunction "TXD_1") (pintype "output"))
    )
    (net (code "20") (name "GND") (class "Default")
      (node (ref "C1") (pin "-") (pinfunction "-_-") (pintype "passive"))
      (node (ref "C10") (pin "1") (pinfunction "P$1_1") (pintype "passive"))
      (node (ref "C11") (pin "2") (pinfunction "P$2_2") (pintype "passive"))
      (node (ref "C12") (pin "2") (pinfunction "P$2_2") (pintype "passive"))
      (node (ref "C13") (pin "1") (pinfunction "P$1_1") (pintype "passive"))
      (node (ref "C14") (pin "1") (pinfunction "P$1_1") (pintype "passive"))
      (node (ref "C15") (pin "1") (pinfunction "P$1_1") (pintype "passive"))
      (node (ref "C16") (pin "1") (pinfunction "P$1_1") (pintype "passive"))
      (node (ref "C17") (pin "1") (pinfunction "P$1_1") (pintype "passive"))
      (node (ref "C18") (pin "1") (pinfunction "P$1_1") (pintype "passive"))
      (node (ref "C19") (pin "1") (pinfunction "P$1_1") (pintype "passive"))
      (node (ref "C2") (pin "-") (pinfunction "-_-") (pintype "passive"))
      (node (ref "C20") (pin "1") (pinfunction "P$1_1") (pintype "passive"))
      (node (ref "C21") (pin "1") (pinfunction "P$1_1") (pintype "passive"))
      (node (ref "C22") (pin "1") (pinfunction "P$1_1") (pintype "passive"))
      (node (ref "C23") (pin "2") (pinfunction "P$2_2") (pintype "passive"))
      (node (ref "C24") (pin "2") (pinfunction "P$2_2") (pintype "passive"))
      (node (ref "C25") (pin "1") (pinfunction "P$1_1") (pintype "passive"))
      (node (ref "C26") (pin "1") (pinfunction "P$1_1") (pintype "passive"))
      (node (ref "C27") (pin "1") (pinfunction "P$1_1") (pintype "passive"))
      (node (ref "C28") (pin "1") (pinfunction "P$1_1") (pintype "passive"))
      (node (ref "C29") (pin "1") (pinfunction "P$1_1") (pintype "passive"))
      (node (ref "C3") (pin "1") (pinfunction "P$1_1") (pintype "passive"))
      (node (ref "C30") (pin "1") (pinfunction "P$1_1") (pintype "passive"))
      (node (ref "C31") (pin "1") (pinfunction "P$1_1") (pintype "passive"))
      (node (ref "C32") (pin "1") (pinfunction "P$1_1") (pintype "passive"))
      (node (ref "C33") (pin "1") (pinfunction "P$1_1") (pintype "passive"))
      (node (ref "C34") (pin "-") (pinfunction "-_-") (pintype "passive"))
      (node (ref "C35") (pin "-") (pinfunction "-_-") (pintype "passive"))
      (node (ref "C36") (pin "-") (pinfunction "-_-") (pintype "passive"))
      (node (ref "C4") (pin "1") (pinfunction "P$1_1") (pintype "passive"))
      (node (ref "C6") (pin "1") (pinfunction "P$1_1") (pintype "passive"))
      (node (ref "C7") (pin "1") (pinfunction "P$1_1") (pintype "passive"))
      (node (ref "C8") (pin "1") (pinfunction "P$1_1") (pintype "passive"))
      (node (ref "C9") (pin "2") (pinfunction "P$2_2") (pintype "passive"))
      (node (ref "CON1") (pin "1") (pinfunction "3_1") (pintype "passive"))
      (node (ref "CON1") (pin "2") (pinfunction "2_2") (pintype "passive"))
      (node (ref "CON2") (pin "11") (pinfunction "CLKS_11") (pintype "bidirectional"))
      (node (ref "CON2") (pin "17") (pinfunction "GND_17") (pintype "bidirectional"))
      (node (ref "CON2") (pin "2") (pinfunction "DATA2S_2") (pintype "bidirectional"))
      (node (ref "CON2") (pin "5") (pinfunction "DATA1S_5") (pintype "bidirectional"))
      (node (ref "CON2") (pin "8") (pinfunction "DATA0S_8") (pintype "bidirectional"))
      (node (ref "CON2") (pin "GND@1") (pinfunction "GND_GND@1") (pintype "power_in"))
      (node (ref "CON2") (pin "GND@2") (pinfunction "GND_GND@2") (pintype "power_in"))
      (node (ref "CON2") (pin "GND@3") (pinfunction "GND_GND@3") (pintype "power_in"))
      (node (ref "CON2") (pin "GND@4") (pinfunction "GND_GND@4") (pintype "power_in"))
      (node (ref "CON3") (pin "1") (pinfunction "LED-K_1") (pintype "bidirectional"))
      (node (ref "CON3") (pin "29") (pinfunction "GND_29") (pintype "bidirectional"))
      (node (ref "CON3") (pin "3") (pinfunction "GND_3") (pintype "bidirectional"))
      (node (ref "CON3") (pin "36") (pinfunction "GND_36") (pintype "bidirectional"))
      (node (ref "CON3") (pin "GND@1") (pinfunction "GND_GND@1") (pintype "power_in"))
      (node (ref "CON3") (pin "GND@2") (pinfunction "GND_GND@2") (pintype "power_in"))
      (node (ref "CON4") (pin "5") (pinfunction "GND_5") (pintype "bidirectional"))
      (node (ref "CON4") (pin "GND@1") (pinfunction "GND_GND@1") (pintype "power_in"))
      (node (ref "CON4") (pin "GND@2") (pinfunction "GND_GND@2") (pintype "power_in"))
      (node (ref "CON4") (pin "GND@3") (pinfunction "GND_GND@3") (pintype "power_in"))
      (node (ref "CON4") (pin "GND@4") (pinfunction "GND_GND@4") (pintype "power_in"))
      (node (ref "CON5") (pin "6") (pinfunction "GND_6") (pintype "bidirectional"))
      (node (ref "CON5") (pin "GND@1") (pinfunction "GND_GND@1") (pintype "power_in"))
      (node (ref "CON5") (pin "GND@2") (pinfunction "GND_GND@2") (pintype "power_in"))
      (node (ref "CON6") (pin "12") (pinfunction "GND_12") (pintype "bidirectional"))
      (node (ref "CON6") (pin "15") (pinfunction "GND_15") (pintype "bidirectional"))
      (node (ref "CON6") (pin "18") (pinfunction "GND_18") (pintype "bidirectional"))
      (node (ref "CON6") (pin "21") (pinfunction "GND_21") (pintype "bidirectional"))
      (node (ref "CON6") (pin "26") (pinfunction "GND_26") (pintype "bidirectional"))
      (node (ref "CON6") (pin "3") (pinfunction "GND_3") (pintype "bidirectional"))
      (node (ref "CON6") (pin "4") (pinfunction "GND_4") (pintype "bidirectional"))
      (node (ref "CON6") (pin "6") (pinfunction "GND_6") (pintype "bidirectional"))
      (node (ref "CON6") (pin "9") (pinfunction "GND_9") (pintype "bidirectional"))
      (node (ref "CON6") (pin "GND@1") (pinfunction "GND_GND@1") (pintype "power_in"))
      (node (ref "CON6") (pin "GND@2") (pinfunction "GND_GND@2") (pintype "power_in"))
      (node (ref "CON6") (pin "GND@3") (pinfunction "GND_GND@3") (pintype "power_in"))
      (node (ref "CON6") (pin "GND@4") (pinfunction "GND_GND@4") (pintype "power_in"))
      (node (ref "IC2") (pin "2") (pinfunction "GND_2") (pintype "bidirectional"))
      (node (ref "IC2") (pin "6") (pinfunction "PGND_6") (pintype "bidirectional"))
      (node (ref "IC4") (pin "1") (pinfunction "A0_1") (pintype "input"))
      (node (ref "IC4") (pin "2") (pinfunction "A1_2") (pintype "input"))
      (node (ref "IC4") (pin "3") (pinfunction "A2_3") (pintype "input"))
      (node (ref "IC4") (pin "4") (pinfunction "GND_4") (pintype "power_in"))
      (node (ref "IC5") (pin "1") (pinfunction "DFO_1") (pintype "bidirectional"))
      (node (ref "IC5") (pin "19") (pinfunction "OGND_19") (pintype "power_in"))
      (node (ref "IC5") (pin "28") (pinfunction "OGND_28") (pintype "power_in"))
      (node (ref "IC5") (pin "3") (pinfunction "ST_3") (pintype "bidirectional"))
      (node (ref "IC5") (pin "39") (pinfunction "DGND_39") (pintype "power_in"))
      (node (ref "IC5") (pin "45") (pinfunction "OGND_45") (pintype "power_in"))
      (node (ref "IC5") (pin "5") (pinfunction "DGND_5") (pintype "power_in"))
      (node (ref "IC5") (pin "58") (pinfunction "OGND_58") (pintype "power_in"))
      (node (ref "IC5") (pin "68") (pinfunction "DGND_68") (pintype "power_in"))
      (node (ref "IC5") (pin "7") (pinfunction "~{STAG}_7") (pintype "bidirectional"))
      (node (ref "IC5") (pin "76") (pinfunction "OGND_76") (pintype "power_in"))
      (node (ref "IC5") (pin "79") (pinfunction "AGND_79") (pintype "power_in"))
      (node (ref "IC5") (pin "83") (pinfunction "AGND_83") (pintype "power_in"))
      (node (ref "IC5") (pin "87") (pinfunction "AGND_87") (pintype "power_in"))
      (node (ref "IC5") (pin "89") (pinfunction "AGND_89") (pintype "power_in"))
      (node (ref "IC5") (pin "92") (pinfunction "AGND_92") (pintype "power_in"))
      (node (ref "IC5") (pin "98") (pinfunction "PGND_98") (pintype "power_in"))
      (node (ref "IC6") (pin "21") (pinfunction "GND_21") (pintype "power_in"))
      (node (ref "IC6") (pin "3") (pinfunction "GND_3") (pintype "power_in"))
      (node (ref "IC6") (pin "5") (pinfunction "GND_5") (pintype "power_in"))
      (node (ref "IC7") (pin "18") (pinfunction "GND_18") (pintype "power_in"))
      (node (ref "IC7") (pin "21") (pinfunction "GND_21") (pintype "power_in"))
      (node (ref "IC7") (pin "25") (pinfunction "GND_25") (pintype "power_in"))
      (node (ref "IC7") (pin "26") (pinfunction "TEST_26") (pintype "input"))
      (node (ref "IC7") (pin "7") (pinfunction "GND_7") (pintype "power_in"))
      (node (ref "IC8") (pin "13") (pinfunction "GND_13") (pintype "power_in"))
      (node (ref "IC8") (pin "21") (pinfunction "GND_21") (pintype "power_in"))
      (node (ref "IC8") (pin "25") (pinfunction "D23_25") (pintype "bidirectional"))
      (node (ref "IC8") (pin "29") (pinfunction "GND_29") (pintype "power_in"))
      (node (ref "IC8") (pin "33") (pinfunction "GND_33") (pintype "power_in"))
      (node (ref "IC8") (pin "35") (pinfunction "GND_35") (pintype "power_in"))
      (node (ref "IC8") (pin "36") (pinfunction "GND_36") (pintype "power_in"))
      (node (ref "IC8") (pin "43") (pinfunction "GND_43") (pintype "power_in"))
      (node (ref "IC8") (pin "49") (pinfunction "GND_49") (pintype "power_in"))
      (node (ref "IC8") (pin "5") (pinfunction "GND_5") (pintype "power_in"))
      (node (ref "IC8") (pin "53") (pinfunction "GND_53") (pintype "power_in"))
      (node (ref "JP1") (pin "1") (pinfunction "1_1") (pintype "passive"))
      (node (ref "JP2") (pin "1") (pinfunction "1_1") (pintype "passive"))
      (node (ref "JP3") (pin "1") (pinfunction "1_1") (pintype "passive"))
      (node (ref "JP5") (pin "1") (pinfunction "1_1") (pintype "passive"))
      (node (ref "JP7") (pin "1") (pinfunction "1_1") (pintype "passive"))
      (node (ref "JP8") (pin "1") (pinfunction "1_1") (pintype "passive"))
      (node (ref "R1") (pin "1") (pinfunction "P$1_1") (pintype "passive"))
      (node (ref "R19") (pin "3") (pinfunction "A_3") (pintype "passive"))
      (node (ref "R25") (pin "1") (pinfunction "P$1_1") (pintype "passive"))
      (node (ref "R27") (pin "1") (pinfunction "P$1_1") (pintype "passive"))
    )
    (net (code "21") (name "HDMI_CLK_N") (class "Default")
      (node (ref "CON2") (pin "12") (pinfunction "CLK-_12") (pintype "bidirectional"))
      (node (ref "IC5") (pin "94") (pinfunction "RXC-_94") (pintype "bidirectional"))
    )
    (net (code "22") (name "HDMI_CLK_P") (class "Default")
      (node (ref "CON2") (pin "10") (pinfunction "CLK+_10") (pintype "bidirectional"))
      (node (ref "IC5") (pin "93") (pinfunction "RXC+_93") (pintype "bidirectional"))
    )
    (net (code "23") (name "HDMI_DAT0_N") (class "Default")
      (node (ref "CON2") (pin "9") (pinfunction "DATA0-_9") (pintype "bidirectional"))
      (node (ref "IC5") (pin "91") (pinfunction "RX0-_91") (pintype "bidirectional"))
    )
    (net (code "24") (name "HDMI_DAT0_P") (class "Default")
      (node (ref "CON2") (pin "7") (pinfunction "DATA0+_7") (pintype "bidirectional"))
      (node (ref "IC5") (pin "90") (pinfunction "RX0+_90") (pintype "bidirectional"))
    )
    (net (code "25") (name "HDMI_DAT1_N") (class "Default")
      (node (ref "CON2") (pin "6") (pinfunction "DATA1-_6") (pintype "bidirectional"))
      (node (ref "IC5") (pin "86") (pinfunction "RX1-_86") (pintype "bidirectional"))
    )
    (net (code "26") (name "HDMI_DAT1_P") (class "Default")
      (node (ref "CON2") (pin "4") (pinfunction "DATA1+_4") (pintype "bidirectional"))
      (node (ref "IC5") (pin "85") (pinfunction "RX1+_85") (pintype "bidirectional"))
    )
    (net (code "27") (name "HDMI_DAT2_N") (class "Default")
      (node (ref "CON2") (pin "3") (pinfunction "DATA2-_3") (pintype "bidirectional"))
      (node (ref "IC5") (pin "81") (pinfunction "RX2-_81") (pintype "bidirectional"))
    )
    (net (code "28") (name "HDMI_DAT2_P") (class "Default")
      (node (ref "CON2") (pin "1") (pinfunction "DATA2+_1") (pintype "bidirectional"))
      (node (ref "IC5") (pin "80") (pinfunction "RX2+_80") (pintype "bidirectional"))
    )
    (net (code "29") (name "HDMI_OCK_INV") (class "Default")
      (node (ref "IC5") (pin "100") (pinfunction "OCK_INV_100") (pintype "bidirectional"))
      (node (ref "JP1") (pin "2") (pinfunction "2_2") (pintype "passive"))
      (node (ref "R6") (pin "1") (pinfunction "P$1_1") (pintype "passive"))
    )
    (net (code "30") (name "HDMI_PIXS") (class "Default")
      (node (ref "IC5") (pin "4") (pinfunction "PIXS_4") (pintype "bidirectional"))
      (node (ref "JP2") (pin "2") (pinfunction "2_2") (pintype "passive"))
      (node (ref "R5") (pin "1") (pinfunction "P$1_1") (pintype "passive"))
    )
    (net (code "31") (name "LVDS_0_N") (class "Default")
      (node (ref "CON6") (pin "7") (pinfunction "RA-_7") (pintype "bidirectional"))
      (node (ref "IC8") (pin "48") (pinfunction "Y0M_48") (pintype "bidirectional"))
    )
    (net (code "32") (name "LVDS_0_P") (class "Default")
      (node (ref "CON6") (pin "8") (pinfunction "RA+_8") (pintype "bidirectional"))
      (node (ref "IC8") (pin "47") (pinfunction "Y0P_47") (pintype "bidirectional"))
    )
    (net (code "33") (name "LVDS_1_N") (class "Default")
      (node (ref "CON6") (pin "10") (pinfunction "RB-_10") (pintype "bidirectional"))
      (node (ref "IC8") (pin "46") (pinfunction "Y1M_46") (pintype "bidirectional"))
    )
    (net (code "34") (name "LVDS_1_P") (class "Default")
      (node (ref "CON6") (pin "11") (pinfunction "RB+_11") (pintype "bidirectional"))
      (node (ref "IC8") (pin "45") (pinfunction "Y1P_45") (pintype "bidirectional"))
    )
    (net (code "35") (name "LVDS_2_N") (class "Default")
      (node (ref "CON6") (pin "13") (pinfunction "RC-_13") (pintype "bidirectional"))
      (node (ref "IC8") (pin "42") (pinfunction "Y2M_42") (pintype "bidirectional"))
    )
    (net (code "36") (name "LVDS_2_P") (class "Default")
      (node (ref "CON6") (pin "14") (pinfunction "RC+_14") (pintype "bidirectional"))
      (node (ref "IC8") (pin "41") (pinfunction "Y2P_41") (pintype "bidirectional"))
    )
    (net (code "37") (name "LVDS_3_N") (class "Default")
      (node (ref "CON6") (pin "19") (pinfunction "RDM-_19") (pintype "bidirectional"))
      (node (ref "IC8") (pin "38") (pinfunction "Y3M_38") (pintype "bidirectional"))
    )
    (net (code "38") (name "LVDS_3_P") (class "Default")
      (node (ref "CON6") (pin "20") (pinfunction "RDM+_20") (pintype "bidirectional"))
      (node (ref "IC8") (pin "37") (pinfunction "Y3P_37") (pintype "bidirectional"))
    )
    (net (code "39") (name "LVDS_CLK_N") (class "Default")
      (node (ref "CON6") (pin "16") (pinfunction "RCLK-_16") (pintype "bidirectional"))
      (node (ref "IC8") (pin "40") (pinfunction "CLKOUTM_40") (pintype "bidirectional"))
    )
    (net (code "40") (name "LVDS_CLK_P") (class "Default")
      (node (ref "CON6") (pin "17") (pinfunction "RCLK+_17") (pintype "bidirectional"))
      (node (ref "IC8") (pin "39") (pinfunction "CLKOUTP_39") (pintype "bidirectional"))
    )
    (net (code "41") (name "LVDS_LED_EN") (class "Default")
      (node (ref "CON6") (pin "25") (pinfunction "LED_EN_25") (pintype "bidirectional"))
      (node (ref "JP8") (pin "2") (pinfunction "2_2") (pintype "passive"))
      (node (ref "R4") (pin "1") (pinfunction "P$1_1") (pintype "passive"))
    )
    (net (code "42") (name "LVDS_PWM") (class "Default")
      (node (ref "CON6") (pin "24") (pinfunction "PWM_24") (pintype "bidirectional"))
      (node (ref "JP6") (pin "3") (pinfunction "3_3") (pintype "passive"))
    )
    (net (code "43") (name "LVDS_REVSCAN") (class "Default")
      (node (ref "CON6") (pin "5") (pinfunction "SHLI_5") (pintype "bidirectional"))
      (node (ref "JP7") (pin "2") (pinfunction "2_2") (pintype "passive"))
      (node (ref "R18") (pin "1") (pinfunction "P$1_1") (pintype "passive"))
    )
    (net (code "44") (name "Net-(C7-P$2)") (class "Default")
      (node (ref "C7") (pin "2") (pinfunction "P$2_2") (pintype "passive"))
      (node (ref "IC6") (pin "7") (pinfunction "PB6(PCINT6/XTAL1/TOSC1)_7") (pintype "bidirectional"))
      (node (ref "Q1") (pin "2") (pinfunction "2_2") (pintype "passive"))
    )
    (net (code "45") (name "Net-(C8-P$2)") (class "Default")
      (node (ref "C8") (pin "2") (pinfunction "P$2_2") (pintype "passive"))
      (node (ref "IC6") (pin "8") (pinfunction "PB7(PCINT7/XTAL2/TOSC2)_8") (pintype "bidirectional"))
      (node (ref "Q1") (pin "1") (pinfunction "1_1") (pintype "passive"))
    )
    (net (code "46") (name "Net-(C11-P$1)") (class "Default")
      (node (ref "C11") (pin "1") (pinfunction "P$1_1") (pintype "passive"))
      (node (ref "IC7") (pin "17") (pinfunction "3V3OUT_17") (pintype "output"))
    )
    (net (code "47") (name "Net-(CON1-1)") (class "Default")
      (node (ref "CON1") (pin "3") (pinfunction "1_3") (pintype "passive"))
      (node (ref "T1") (pin "2") (pinfunction "D_2") (pintype "passive"))
    )
    (net (code "48") (name "Net-(CON2-DETECT)") (class "Default")
      (node (ref "CON2") (pin "19") (pinfunction "DETECT_19") (pintype "bidirectional"))
      (node (ref "R7") (pin "1") (pinfunction "P$1_1") (pintype "passive"))
    )
    (net (code "49") (name "Net-(CON3-LED-A)") (class "Default")
      (node (ref "CON3") (pin "2") (pinfunction "LED-A_2") (pintype "bidirectional"))
      (node (ref "T2") (pin "2") (pinfunction "S_2") (pintype "passive"))
    )
    (net (code "50") (name "Net-(IC5-DE)") (class "Default")
      (node (ref "IC5") (pin "46") (pinfunction "DE_46") (pintype "bidirectional"))
      (node (ref "R2") (pin "3M") (pinfunction "3M_3M") (pintype "bidirectional"))
    )
    (net (code "51") (name "Net-(IC5-HSYNC)") (class "Default")
      (node (ref "IC5") (pin "48") (pinfunction "HSYNC_48") (pintype "bidirectional"))
      (node (ref "R2") (pin "1M") (pinfunction "1M_1M") (pintype "bidirectional"))
    )
    (net (code "52") (name "Net-(IC5-ODCK)") (class "Default")
      (node (ref "IC5") (pin "44") (pinfunction "ODCK_44") (pintype "bidirectional"))
      (node (ref "R2") (pin "4M") (pinfunction "4M_4M") (pintype "bidirectional"))
    )
    (net (code "53") (name "Net-(IC5-QE0)") (class "Default")
      (node (ref "IC5") (pin "10") (pinfunction "QE0_10") (pintype "bidirectional"))
      (node (ref "R3") (pin "4M") (pinfunction "4M_4M") (pintype "bidirectional"))
    )
    (net (code "54") (name "Net-(IC5-QE1)") (class "Default")
      (node (ref "IC5") (pin "11") (pinfunction "QE1_11") (pintype "bidirectional"))
      (node (ref "R3") (pin "3M") (pinfunction "3M_3M") (pintype "bidirectional"))
    )
    (net (code "55") (name "Net-(IC5-QE2)") (class "Default")
      (node (ref "IC5") (pin "12") (pinfunction "QE2_12") (pintype "bidirectional"))
      (node (ref "R3") (pin "2M") (pinfunction "2M_2M") (pintype "bidirectional"))
    )
    (net (code "56") (name "Net-(IC5-QE3)") (class "Default")
      (node (ref "IC5") (pin "13") (pinfunction "QE3_13") (pintype "bidirectional"))
      (node (ref "R3") (pin "1M") (pinfunction "1M_1M") (pintype "bidirectional"))
    )
    (net (code "57") (name "Net-(IC5-QE4)") (class "Default")
      (node (ref "IC5") (pin "14") (pinfunction "QE4_14") (pintype "bidirectional"))
      (node (ref "R8") (pin "4M") (pinfunction "4M_4M") (pintype "bidirectional"))
    )
    (net (code "58") (name "Net-(IC5-QE5)") (class "Default")
      (node (ref "IC5") (pin "15") (pinfunction "QE5_15") (pintype "bidirectional"))
      (node (ref "R8") (pin "3M") (pinfunction "3M_3M") (pintype "bidirectional"))
    )
    (net (code "59") (name "Net-(IC5-QE6)") (class "Default")
      (node (ref "IC5") (pin "16") (pinfunction "QE6_16") (pintype "bidirectional"))
      (node (ref "R8") (pin "2M") (pinfunction "2M_2M") (pintype "bidirectional"))
    )
    (net (code "60") (name "Net-(IC5-QE7)") (class "Default")
      (node (ref "IC5") (pin "17") (pinfunction "QE7_17") (pintype "bidirectional"))
      (node (ref "R8") (pin "1M") (pinfunction "1M_1M") (pintype "bidirectional"))
    )
    (net (code "61") (name "Net-(IC5-QE8)") (class "Default")
      (node (ref "IC5") (pin "20") (pinfunction "QE8_20") (pintype "bidirectional"))
      (node (ref "R9") (pin "4M") (pinfunction "4M_4M") (pintype "bidirectional"))
    )
    (net (code "62") (name "Net-(IC5-QE9)") (class "Default")
      (node (ref "IC5") (pin "21") (pinfunction "QE9_21") (pintype "bidirectional"))
      (node (ref "R9") (pin "3M") (pinfunction "3M_3M") (pintype "bidirectional"))
    )
    (net (code "63") (name "Net-(IC5-QE10)") (class "Default")
      (node (ref "IC5") (pin "22") (pinfunction "QE10_22") (pintype "bidirectional"))
      (node (ref "R9") (pin "2M") (pinfunction "2M_2M") (pintype "bidirectional"))
    )
    (net (code "64") (name "Net-(IC5-QE11)") (class "Default")
      (node (ref "IC5") (pin "23") (pinfunction "QE11_23") (pintype "bidirectional"))
      (node (ref "R9") (pin "1M") (pinfunction "1M_1M") (pintype "bidirectional"))
    )
    (net (code "65") (name "Net-(IC5-QE12)") (class "Default")
      (node (ref "IC5") (pin "24") (pinfunction "QE12_24") (pintype "bidirectional"))
      (node (ref "R10") (pin "4M") (pinfunction "4M_4M") (pintype "bidirectional"))
    )
    (net (code "66") (name "Net-(IC5-QE13)") (class "Default")
      (node (ref "IC5") (pin "25") (pinfunction "QE13_25") (pintype "bidirectional"))
      (node (ref "R10") (pin "3M") (pinfunction "3M_3M") (pintype "bidirectional"))
    )
    (net (code "67") (name "Net-(IC5-QE14)") (class "Default")
      (node (ref "IC5") (pin "26") (pinfunction "QE14_26") (pintype "bidirectional"))
      (node (ref "R10") (pin "2M") (pinfunction "2M_2M") (pintype "bidirectional"))
    )
    (net (code "68") (name "Net-(IC5-QE15)") (class "Default")
      (node (ref "IC5") (pin "27") (pinfunction "QE15_27") (pintype "bidirectional"))
      (node (ref "R10") (pin "1M") (pinfunction "1M_1M") (pintype "bidirectional"))
    )
    (net (code "69") (name "Net-(IC5-QE16)") (class "Default")
      (node (ref "IC5") (pin "30") (pinfunction "QE16_30") (pintype "bidirectional"))
      (node (ref "R11") (pin "4M") (pinfunction "4M_4M") (pintype "bidirectional"))
    )
    (net (code "70") (name "Net-(IC5-QE17)") (class "Default")
      (node (ref "IC5") (pin "31") (pinfunction "QE17_31") (pintype "bidirectional"))
      (node (ref "R11") (pin "3M") (pinfunction "3M_3M") (pintype "bidirectional"))
    )
    (net (code "71") (name "Net-(IC5-QE18)") (class "Default")
      (node (ref "IC5") (pin "32") (pinfunction "QE18_32") (pintype "bidirectional"))
      (node (ref "R11") (pin "2M") (pinfunction "2M_2M") (pintype "bidirectional"))
    )
    (net (code "72") (name "Net-(IC5-QE19)") (class "Default")
      (node (ref "IC5") (pin "33") (pinfunction "QE19_33") (pintype "bidirectional"))
      (node (ref "R11") (pin "1M") (pinfunction "1M_1M") (pintype "bidirectional"))
    )
    (net (code "73") (name "Net-(IC5-QE20)") (class "Default")
      (node (ref "IC5") (pin "34") (pinfunction "QE20_34") (pintype "bidirectional"))
      (node (ref "R12") (pin "4M") (pinfunction "4M_4M") (pintype "bidirectional"))
    )
    (net (code "74") (name "Net-(IC5-QE21)") (class "Default")
      (node (ref "IC5") (pin "35") (pinfunction "QE21_35") (pintype "bidirectional"))
      (node (ref "R12") (pin "3M") (pinfunction "3M_3M") (pintype "bidirectional"))
    )
    (net (code "75") (name "Net-(IC5-QE22)") (class "Default")
      (node (ref "IC5") (pin "36") (pinfunction "QE22_36") (pintype "bidirectional"))
      (node (ref "R12") (pin "2M") (pinfunction "2M_2M") (pintype "bidirectional"))
    )
    (net (code "76") (name "Net-(IC5-QE23)") (class "Default")
      (node (ref "IC5") (pin "37") (pinfunction "QE23_37") (pintype "bidirectional"))
      (node (ref "R12") (pin "1M") (pinfunction "1M_1M") (pintype "bidirectional"))
    )
    (net (code "77") (name "Net-(IC5-VSYNC)") (class "Default")
      (node (ref "IC5") (pin "47") (pinfunction "VSYNC_47") (pintype "bidirectional"))
      (node (ref "R2") (pin "2M") (pinfunction "2M_2M") (pintype "bidirectional"))
    )
    (net (code "78") (name "Net-(IC7-USBDM)") (class "Default")
      (node (ref "IC7") (pin "16") (pinfunction "USBDM_16") (pintype "bidirectional"))
      (node (ref "R23") (pin "2") (pinfunction "P$2_2") (pintype "passive"))
    )
    (net (code "79") (name "Net-(IC7-USBDP)") (class "Default")
      (node (ref "IC7") (pin "15") (pinfunction "USBDP_15") (pintype "bidirectional"))
      (node (ref "R22") (pin "2") (pinfunction "P$2_2") (pintype "passive"))
    )
    (net (code "80") (name "Net-(R1-P$2)") (class "Default")
      (node (ref "R1") (pin "2") (pinfunction "P$2_2") (pintype "passive"))
      (node (ref "T1") (pin "1") (pinfunction "G_1") (pintype "passive"))
    )
    (net (code "81") (name "Net-(R20-P$1)") (class "Default")
      (node (ref "R20") (pin "1") (pinfunction "P$1_1") (pintype "passive"))
      (node (ref "T2") (pin "3") (pinfunction "D_3") (pintype "passive"))
    )
    (net (code "82") (name "Net-(R25-P$2)") (class "Default")
      (node (ref "LED2") (pin "A") (pinfunction "A_A") (pintype "passive"))
      (node (ref "R25") (pin "2") (pinfunction "P$2_2") (pintype "passive"))
    )
    (net (code "83") (name "Net-(R27-P$2)") (class "Default")
      (node (ref "LED4") (pin "A") (pinfunction "A_A") (pintype "passive"))
      (node (ref "R27") (pin "2") (pinfunction "P$2_2") (pintype "passive"))
    )
    (net (code "84") (name "RGB_DE") (class "Default")
      (node (ref "CON3") (pin "34") (pinfunction "DEN_34") (pintype "bidirectional"))
      (node (ref "IC8") (pin "30") (pinfunction "D26_30") (pintype "bidirectional"))
      (node (ref "R2") (pin "3P") (pinfunction "3P_3P") (pintype "bidirectional"))
    )
    (net (code "85") (name "RGB_DISP") (class "Default")
      (node (ref "CON3") (pin "31") (pinfunction "DISP_31") (pintype "bidirectional"))
      (node (ref "JP3") (pin "2") (pinfunction "2_2") (pintype "passive"))
      (node (ref "R15") (pin "1") (pinfunction "P$1_1") (pintype "passive"))
    )
    (net (code "86") (name "RGB_EVEN_B0") (class "Default")
      (node (ref "CON3") (pin "21") (pinfunction "B0_21") (pintype "bidirectional"))
      (node (ref "IC8") (pin "15") (pinfunction "D15_15") (pintype "bidirectional"))
      (node (ref "R3") (pin "4P") (pinfunction "4P_4P") (pintype "bidirectional"))
    )
    (net (code "87") (name "RGB_EVEN_B1") (class "Default")
      (node (ref "CON3") (pin "22") (pinfunction "B1_22") (pintype "bidirectional"))
      (node (ref "IC8") (pin "19") (pinfunction "D18_19") (pintype "bidirectional"))
      (node (ref "R3") (pin "3P") (pinfunction "3P_3P") (pintype "bidirectional"))
    )
    (net (code "88") (name "RGB_EVEN_B2") (class "Default")
      (node (ref "CON3") (pin "23") (pinfunction "B2_23") (pintype "bidirectional"))
      (node (ref "IC8") (pin "20") (pinfunction "D19_20") (pintype "bidirectional"))
      (node (ref "R3") (pin "2P") (pinfunction "2P_2P") (pintype "bidirectional"))
    )
    (net (code "89") (name "RGB_EVEN_B3") (class "Default")
      (node (ref "CON3") (pin "24") (pinfunction "B3_24") (pintype "bidirectional"))
      (node (ref "IC8") (pin "22") (pinfunction "D20_22") (pintype "bidirectional"))
      (node (ref "R3") (pin "1P") (pinfunction "1P_1P") (pintype "bidirectional"))
    )
    (net (code "90") (name "RGB_EVEN_B4") (class "Default")
      (node (ref "CON3") (pin "25") (pinfunction "B4_25") (pintype "bidirectional"))
      (node (ref "IC8") (pin "23") (pinfunction "D21_23") (pintype "bidirectional"))
      (node (ref "R8") (pin "4P") (pinfunction "4P_4P") (pintype "bidirectional"))
    )
    (net (code "91") (name "RGB_EVEN_B5") (class "Default")
      (node (ref "CON3") (pin "26") (pinfunction "B5_26") (pintype "bidirectional"))
      (node (ref "IC8") (pin "24") (pinfunction "D22_24") (pintype "bidirectional"))
      (node (ref "R8") (pin "3P") (pinfunction "3P_3P") (pintype "bidirectional"))
    )
    (net (code "92") (name "RGB_EVEN_B6") (class "Default")
      (node (ref "CON3") (pin "27") (pinfunction "B6_27") (pintype "bidirectional"))
      (node (ref "IC8") (pin "16") (pinfunction "D16_16") (pintype "bidirectional"))
      (node (ref "R8") (pin "2P") (pinfunction "2P_2P") (pintype "bidirectional"))
    )
    (net (code "93") (name "RGB_EVEN_B7") (class "Default")
      (node (ref "CON3") (pin "28") (pinfunction "B7_28") (pintype "bidirectional"))
      (node (ref "IC8") (pin "18") (pinfunction "D17_18") (pintype "bidirectional"))
      (node (ref "R8") (pin "1P") (pinfunction "1P_1P") (pintype "bidirectional"))
    )
    (net (code "94") (name "RGB_EVEN_G0") (class "Default")
      (node (ref "CON3") (pin "13") (pinfunction "G0_13") (pintype "bidirectional"))
      (node (ref "IC8") (pin "4") (pinfunction "D7_4") (pintype "bidirectional"))
      (node (ref "R9") (pin "4P") (pinfunction "4P_4P") (pintype "bidirectional"))
    )
    (net (code "95") (name "RGB_EVEN_G1") (class "Default")
      (node (ref "CON3") (pin "14") (pinfunction "G1_14") (pintype "bidirectional"))
      (node (ref "IC8") (pin "6") (pinfunction "D8_6") (pintype "bidirectional"))
      (node (ref "R9") (pin "3P") (pinfunction "3P_3P") (pintype "bidirectional"))
    )
    (net (code "96") (name "RGB_EVEN_G2") (class "Default")
      (node (ref "CON3") (pin "15") (pinfunction "G2_15") (pintype "bidirectional"))
      (node (ref "IC8") (pin "7") (pinfunction "D9_7") (pintype "bidirectional"))
      (node (ref "R9") (pin "2P") (pinfunction "2P_2P") (pintype "bidirectional"))
    )
    (net (code "97") (name "RGB_EVEN_G3") (class "Default")
      (node (ref "CON3") (pin "16") (pinfunction "G3_16") (pintype "bidirectional"))
      (node (ref "IC8") (pin "11") (pinfunction "D12_11") (pintype "bidirectional"))
      (node (ref "R9") (pin "1P") (pinfunction "1P_1P") (pintype "bidirectional"))
    )
    (net (code "98") (name "RGB_EVEN_G4") (class "Default")
      (node (ref "CON3") (pin "17") (pinfunction "G4_17") (pintype "bidirectional"))
      (node (ref "IC8") (pin "12") (pinfunction "D13_12") (pintype "bidirectional"))
      (node (ref "R10") (pin "4P") (pinfunction "4P_4P") (pintype "bidirectional"))
    )
    (net (code "99") (name "RGB_EVEN_G5") (class "Default")
      (node (ref "CON3") (pin "18") (pinfunction "G5_18") (pintype "bidirectional"))
      (node (ref "IC8") (pin "14") (pinfunction "D14_14") (pintype "bidirectional"))
      (node (ref "R10") (pin "3P") (pinfunction "3P_3P") (pintype "bidirectional"))
    )
    (net (code "100") (name "RGB_EVEN_G6") (class "Default")
      (node (ref "CON3") (pin "19") (pinfunction "G6_19") (pintype "bidirectional"))
      (node (ref "IC8") (pin "8") (pinfunction "D10_8") (pintype "bidirectional"))
      (node (ref "R10") (pin "2P") (pinfunction "2P_2P") (pintype "bidirectional"))
    )
    (net (code "101") (name "RGB_EVEN_G7") (class "Default")
      (node (ref "CON3") (pin "20") (pinfunction "G7_20") (pintype "bidirectional"))
      (node (ref "IC8") (pin "10") (pinfunction "D11_10") (pintype "bidirectional"))
      (node (ref "R10") (pin "1P") (pinfunction "1P_1P") (pintype "bidirectional"))
    )
    (net (code "102") (name "RGB_EVEN_R0") (class "Default")
      (node (ref "CON3") (pin "5") (pinfunction "R0_5") (pintype "bidirectional"))
      (node (ref "IC8") (pin "51") (pinfunction "D0_51") (pintype "bidirectional"))
      (node (ref "R11") (pin "4P") (pinfunction "4P_4P") (pintype "bidirectional"))
    )
    (net (code "103") (name "RGB_EVEN_R1") (class "Default")
      (node (ref "CON3") (pin "6") (pinfunction "R1_6") (pintype "bidirectional"))
      (node (ref "IC8") (pin "52") (pinfunction "D1_52") (pintype "bidirectional"))
      (node (ref "R11") (pin "3P") (pinfunction "3P_3P") (pintype "bidirectional"))
    )
    (net (code "104") (name "RGB_EVEN_R2") (class "Default")
      (node (ref "CON3") (pin "7") (pinfunction "R2_7") (pintype "bidirectional"))
      (node (ref "IC8") (pin "54") (pinfunction "D2_54") (pintype "bidirectional"))
      (node (ref "R11") (pin "2P") (pinfunction "2P_2P") (pintype "bidirectional"))
    )
    (net (code "105") (name "RGB_EVEN_R3") (class "Default")
      (node (ref "CON3") (pin "8") (pinfunction "R3_8") (pintype "bidirectional"))
      (node (ref "IC8") (pin "55") (pinfunction "D3_55") (pintype "bidirectional"))
      (node (ref "R11") (pin "1P") (pinfunction "1P_1P") (pintype "bidirectional"))
    )
    (net (code "106") (name "RGB_EVEN_R4") (class "Default")
      (node (ref "CON3") (pin "9") (pinfunction "R4_9") (pintype "bidirectional"))
      (node (ref "IC8") (pin "56") (pinfunction "D4_56") (pintype "bidirectional"))
      (node (ref "R12") (pin "4P") (pinfunction "4P_4P") (pintype "bidirectional"))
    )
    (net (code "107") (name "RGB_EVEN_R5") (class "Default")
      (node (ref "CON3") (pin "10") (pinfunction "R5_10") (pintype "bidirectional"))
      (node (ref "IC8") (pin "3") (pinfunction "D6_3") (pintype "bidirectional"))
      (node (ref "R12") (pin "3P") (pinfunction "3P_3P") (pintype "bidirectional"))
    )
    (net (code "108") (name "RGB_EVEN_R6") (class "Default")
      (node (ref "CON3") (pin "11") (pinfunction "R6_11") (pintype "bidirectional"))
      (node (ref "IC8") (pin "50") (pinfunction "D27_50") (pintype "bidirectional"))
      (node (ref "R12") (pin "2P") (pinfunction "2P_2P") (pintype "bidirectional"))
    )
    (net (code "109") (name "RGB_EVEN_R7") (class "Default")
      (node (ref "CON3") (pin "12") (pinfunction "R7_12") (pintype "bidirectional"))
      (node (ref "IC8") (pin "2") (pinfunction "D5_2") (pintype "bidirectional"))
      (node (ref "R12") (pin "1P") (pinfunction "1P_1P") (pintype "bidirectional"))
    )
    (net (code "110") (name "RGB_HSYNC") (class "Default")
      (node (ref "CON3") (pin "32") (pinfunction "HSYNC_32") (pintype "bidirectional"))
      (node (ref "IC8") (pin "27") (pinfunction "D24_27") (pintype "bidirectional"))
      (node (ref "R2") (pin "2P") (pinfunction "2P_2P") (pintype "bidirectional"))
    )
    (net (code "111") (name "RGB_ODCK") (class "Default")
      (node (ref "CON3") (pin "30") (pinfunction "CLK_30") (pintype "bidirectional"))
      (node (ref "R2") (pin "4P") (pinfunction "4P_4P") (pintype "bidirectional"))
    )
    (net (code "112") (name "RGB_PWM") (class "Default")
      (node (ref "JP4") (pin "3") (pinfunction "3_3") (pintype "passive"))
      (node (ref "JP6") (pin "1") (pinfunction "1_1") (pintype "passive"))
    )
    (net (code "113") (name "RGB_PWM_EN") (class "Default")
      (node (ref "JP4") (pin "2") (pinfunction "2_2") (pintype "passive"))
      (node (ref "T2") (pin "1") (pinfunction "G_1") (pintype "passive"))
    )
    (net (code "114") (name "RGB_VSYNC") (class "Default")
      (node (ref "CON3") (pin "33") (pinfunction "VSYNC_33") (pintype "bidirectional"))
      (node (ref "IC8") (pin "28") (pinfunction "D25_28") (pintype "bidirectional"))
      (node (ref "R2") (pin "1P") (pinfunction "1P_1P") (pintype "bidirectional"))
    )
    (net (code "115") (name "USB_D+") (class "Default")
      (node (ref "CON4") (pin "3") (pinfunction "D+_3") (pintype "bidirectional"))
      (node (ref "R23") (pin "1") (pinfunction "P$1_1") (pintype "passive"))
    )
    (net (code "116") (name "USB_D-") (class "Default")
      (node (ref "CON4") (pin "2") (pinfunction "D-_2") (pintype "bidirectional"))
      (node (ref "R22") (pin "1") (pinfunction "P$1_1") (pintype "passive"))
    )
    (net (code "117") (name "unconnected-(C5-Pad+)") (class "Default")
      (node (ref "C5") (pin "+") (pinfunction "+_+") (pintype "passive"))
    )
    (net (code "118") (name "unconnected-(C5-Pad-)") (class "Default")
      (node (ref "C5") (pin "-") (pinfunction "-_-") (pintype "passive"))
    )
    (net (code "119") (name "unconnected-(CON2-CEC-Pad13)") (class "Default")
      (node (ref "CON2") (pin "13") (pinfunction "CEC_13") (pintype "bidirectional"))
    )
    (net (code "120") (name "unconnected-(CON2-NC-Pad14)") (class "Default")
      (node (ref "CON2") (pin "14") (pinfunction "NC_14") (pintype "bidirectional"))
    )
    (net (code "121") (name "unconnected-(CON3-NC-Pad35)") (class "Default")
      (node (ref "CON3") (pin "35") (pinfunction "NC_35") (pintype "bidirectional"))
    )
    (net (code "122") (name "unconnected-(CON3-XL-Pad39)") (class "Default")
      (node (ref "CON3") (pin "39") (pinfunction "XL_39") (pintype "bidirectional"))
    )
    (net (code "123") (name "unconnected-(CON3-XR-Pad37)") (class "Default")
      (node (ref "CON3") (pin "37") (pinfunction "XR_37") (pintype "bidirectional"))
    )
    (net (code "124") (name "unconnected-(CON3-YD-Pad38)") (class "Default")
      (node (ref "CON3") (pin "38") (pinfunction "YD_38") (pintype "bidirectional"))
    )
    (net (code "125") (name "unconnected-(CON3-YU-Pad40)") (class "Default")
      (node (ref "CON3") (pin "40") (pinfunction "YU_40") (pintype "bidirectional"))
    )
    (net (code "126") (name "unconnected-(CON4-ID-Pad4)") (class "Default")
      (node (ref "CON4") (pin "4") (pinfunction "ID_4") (pintype "bidirectional"))
    )
    (net (code "127") (name "unconnected-(CON6-NC-Pad27)") (class "Default")
      (node (ref "CON6") (pin "27") (pinfunction "NC_27") (pintype "bidirectional"))
    )
    (net (code "128") (name "unconnected-(CON6-TP-Pad22)") (class "Default")
      (node (ref "CON6") (pin "22") (pinfunction "TP_22") (pintype "bidirectional"))
    )
    (net (code "129") (name "unconnected-(CON6-TP-Pad23)") (class "Default")
      (node (ref "CON6") (pin "23") (pinfunction "TP_23") (pintype "bidirectional"))
    )
    (net (code "130") (name "unconnected-(IC2-EN-Pad5)") (class "Default")
      (node (ref "IC2") (pin "5") (pinfunction "EN_5") (pintype "bidirectional"))
    )
    (net (code "131") (name "unconnected-(IC2-PG-Pad4)") (class "Default")
      (node (ref "IC2") (pin "4") (pinfunction "PG_4") (pintype "bidirectional"))
    )
    (net (code "132") (name "unconnected-(IC5-CTL1-Pad40)") (class "Default")
      (node (ref "IC5") (pin "40") (pinfunction "CTL1_40") (pintype "bidirectional"))
    )
    (net (code "133") (name "unconnected-(IC5-CTL2-Pad41)") (class "Default")
      (node (ref "IC5") (pin "41") (pinfunction "CTL2_41") (pintype "bidirectional"))
    )
    (net (code "134") (name "unconnected-(IC5-CTL3-Pad42)") (class "Default")
      (node (ref "IC5") (pin "42") (pinfunction "CTL3_42") (pintype "bidirectional"))
    )
    (net (code "135") (name "unconnected-(IC5-EXT_RES-Pad96)") (class "Default")
      (node (ref "IC5") (pin "96") (pinfunction "EXT_RES_96") (pintype "bidirectional"))
    )
    (net (code "136") (name "unconnected-(IC5-QO0-Pad49)") (class "Default")
      (node (ref "IC5") (pin "49") (pinfunction "QO0_49") (pintype "bidirectional"))
    )
    (net (code "137") (name "unconnected-(IC5-QO1-Pad50)") (class "Default")
      (node (ref "IC5") (pin "50") (pinfunction "QO1_50") (pintype "bidirectional"))
    )
    (net (code "138") (name "unconnected-(IC5-QO2-Pad51)") (class "Default")
      (node (ref "IC5") (pin "51") (pinfunction "QO2_51") (pintype "bidirectional"))
    )
    (net (code "139") (name "unconnected-(IC5-QO3-Pad52)") (class "Default")
      (node (ref "IC5") (pin "52") (pinfunction "QO3_52") (pintype "bidirectional"))
    )
    (net (code "140") (name "unconnected-(IC5-QO4-Pad53)") (class "Default")
      (node (ref "IC5") (pin "53") (pinfunction "QO4_53") (pintype "bidirectional"))
    )
    (net (code "141") (name "unconnected-(IC5-QO5-Pad54)") (class "Default")
      (node (ref "IC5") (pin "54") (pinfunction "QO5_54") (pintype "bidirectional"))
    )
    (net (code "142") (name "unconnected-(IC5-QO6-Pad55)") (class "Default")
      (node (ref "IC5") (pin "55") (pinfunction "QO6_55") (pintype "bidirectional"))
    )
    (net (code "143") (name "unconnected-(IC5-QO7-Pad56)") (class "Default")
      (node (ref "IC5") (pin "56") (pinfunction "QO7_56") (pintype "bidirectional"))
    )
    (net (code "144") (name "unconnected-(IC5-QO8-Pad59)") (class "Default")
      (node (ref "IC5") (pin "59") (pinfunction "QO8_59") (pintype "bidirectional"))
    )
    (net (code "145") (name "unconnected-(IC5-QO9-Pad60)") (class "Default")
      (node (ref "IC5") (pin "60") (pinfunction "QO9_60") (pintype "bidirectional"))
    )
    (net (code "146") (name "unconnected-(IC5-QO10-Pad61)") (class "Default")
      (node (ref "IC5") (pin "61") (pinfunction "QO10_61") (pintype "bidirectional"))
    )
    (net (code "147") (name "unconnected-(IC5-QO11-Pad62)") (class "Default")
      (node (ref "IC5") (pin "62") (pinfunction "QO11_62") (pintype "bidirectional"))
    )
    (net (code "148") (name "unconnected-(IC5-QO12-Pad63)") (class "Default")
      (node (ref "IC5") (pin "63") (pinfunction "QO12_63") (pintype "bidirectional"))
    )
    (net (code "149") (name "unconnected-(IC5-QO13-Pad64)") (class "Default")
      (node (ref "IC5") (pin "64") (pinfunction "QO13_64") (pintype "bidirectional"))
    )
    (net (code "150") (name "unconnected-(IC5-QO14-Pad65)") (class "Default")
      (node (ref "IC5") (pin "65") (pinfunction "QO14_65") (pintype "bidirectional"))
    )
    (net (code "151") (name "unconnected-(IC5-QO15-Pad66)") (class "Default")
      (node (ref "IC5") (pin "66") (pinfunction "QO15_66") (pintype "bidirectional"))
    )
    (net (code "152") (name "unconnected-(IC5-QO16-Pad69)") (class "Default")
      (node (ref "IC5") (pin "69") (pinfunction "QO16_69") (pintype "bidirectional"))
    )
    (net (code "153") (name "unconnected-(IC5-QO17-Pad70)") (class "Default")
      (node (ref "IC5") (pin "70") (pinfunction "QO17_70") (pintype "bidirectional"))
    )
    (net (code "154") (name "unconnected-(IC5-QO18-Pad71)") (class "Default")
      (node (ref "IC5") (pin "71") (pinfunction "QO18_71") (pintype "bidirectional"))
    )
    (net (code "155") (name "unconnected-(IC5-QO19-Pad72)") (class "Default")
      (node (ref "IC5") (pin "72") (pinfunction "QO19_72") (pintype "bidirectional"))
    )
    (net (code "156") (name "unconnected-(IC5-QO20-Pad73)") (class "Default")
      (node (ref "IC5") (pin "73") (pinfunction "QO20_73") (pintype "bidirectional"))
    )
    (net (code "157") (name "unconnected-(IC5-QO21-Pad74)") (class "Default")
      (node (ref "IC5") (pin "74") (pinfunction "QO21_74") (pintype "bidirectional"))
    )
    (net (code "158") (name "unconnected-(IC5-QO22-Pad75)") (class "Default")
      (node (ref "IC5") (pin "75") (pinfunction "QO22_75") (pintype "bidirectional"))
    )
    (net (code "159") (name "unconnected-(IC5-QO23-Pad77)") (class "Default")
      (node (ref "IC5") (pin "77") (pinfunction "QO23_77") (pintype "bidirectional"))
    )
    (net (code "160") (name "unconnected-(IC5-SCDT-Pad8)") (class "Default")
      (node (ref "IC5") (pin "8") (pinfunction "SCDT_8") (pintype "bidirectional"))
    )
    (net (code "161") (name "unconnected-(IC5-~{PDO}-Pad9)") (class "Default")
      (node (ref "IC5") (pin "9") (pinfunction "~{PDO}_9") (pintype "bidirectional"))
    )
    (net (code "162") (name "unconnected-(IC5-~{PD}-Pad2)") (class "Default")
      (node (ref "IC5") (pin "2") (pinfunction "~{PD}_2") (pintype "bidirectional"))
    )
    (net (code "163") (name "unconnected-(IC6-(PCINT18{slash}INT0)PD2-Pad32)") (class "Default")
      (node (ref "IC6") (pin "32") (pinfunction "(PCINT18/INT0)PD2_32") (pintype "bidirectional"))
    )
    (net (code "164") (name "unconnected-(IC6-(PCINT19{slash}OC2B{slash}INT1)PD3-Pad1)") (class "Default")
      (node (ref "IC6") (pin "1") (pinfunction "(PCINT19/OC2B/INT1)PD3_1") (pintype "bidirectional"))
    )
    (net (code "165") (name "unconnected-(IC6-(PCINT20{slash}XCK{slash}T0)PD4-Pad2)") (class "Default")
      (node (ref "IC6") (pin "2") (pinfunction "(PCINT20/XCK/T0)PD4_2") (pintype "bidirectional"))
    )
    (net (code "166") (name "unconnected-(IC6-(PCINT21{slash}OC0B{slash}T1)PD5-Pad9)") (class "Default")
      (node (ref "IC6") (pin "9") (pinfunction "(PCINT21/OC0B/T1)PD5_9") (pintype "bidirectional"))
    )
    (net (code "167") (name "unconnected-(IC6-(PCINT22{slash}OC0A{slash}AIN0)PD6-Pad10)") (class "Default")
      (node (ref "IC6") (pin "10") (pinfunction "(PCINT22/OC0A/AIN0)PD6_10") (pintype "bidirectional"))
    )
    (net (code "168") (name "unconnected-(IC6-(PCINT23{slash}AIN1)PD7-Pad11)") (class "Default")
      (node (ref "IC6") (pin "11") (pinfunction "(PCINT23/AIN1)PD7_11") (pintype "bidirectional"))
    )
    (net (code "169") (name "unconnected-(IC6-ADC6-Pad19)") (class "Default")
      (node (ref "IC6") (pin "19") (pinfunction "ADC6_19") (pintype "bidirectional"))
    )
    (net (code "170") (name "unconnected-(IC6-ADC7-Pad22)") (class "Default")
      (node (ref "IC6") (pin "22") (pinfunction "ADC7_22") (pintype "bidirectional"))
    )
    (net (code "171") (name "unconnected-(IC6-PB0(PCINT0{slash}CLKO{slash}ICP1)-Pad12)") (class "Default")
      (node (ref "IC6") (pin "12") (pinfunction "PB0(PCINT0/CLKO/ICP1)_12") (pintype "bidirectional"))
    )
    (net (code "172") (name "unconnected-(IC6-PB2(SS{slash}OC1B{slash}PCINT2)-Pad14)") (class "Default")
      (node (ref "IC6") (pin "14") (pinfunction "PB2(SS/OC1B/PCINT2)_14") (pintype "bidirectional"))
    )
    (net (code "173") (name "unconnected-(IC6-PC1(ADC1{slash}PCINT9)-Pad24)") (class "Default")
      (node (ref "IC6") (pin "24") (pinfunction "PC1(ADC1/PCINT9)_24") (pintype "bidirectional"))
    )
    (net (code "174") (name "unconnected-(IC6-PC2(ADC2{slash}PCINT10)-Pad25)") (class "Default")
      (node (ref "IC6") (pin "25") (pinfunction "PC2(ADC2/PCINT10)_25") (pintype "bidirectional"))
    )
    (net (code "175") (name "unconnected-(IC6-PC3(ADC3{slash}PCINT11)-Pad26)") (class "Default")
      (node (ref "IC6") (pin "26") (pinfunction "PC3(ADC3/PCINT11)_26") (pintype "bidirectional"))
    )
    (net (code "176") (name "unconnected-(IC7-CBUS0-Pad23)") (class "Default")
      (node (ref "IC7") (pin "23") (pinfunction "CBUS0_23") (pintype "bidirectional"))
    )
    (net (code "177") (name "unconnected-(IC7-CBUS1-Pad22)") (class "Default")
      (node (ref "IC7") (pin "22") (pinfunction "CBUS1_22") (pintype "bidirectional"))
    )
    (net (code "178") (name "unconnected-(IC7-CBUS2-Pad13)") (class "Default")
      (node (ref "IC7") (pin "13") (pinfunction "CBUS2_13") (pintype "bidirectional"))
    )
    (net (code "179") (name "unconnected-(IC7-CBUS3-Pad14)") (class "Default")
      (node (ref "IC7") (pin "14") (pinfunction "CBUS3_14") (pintype "bidirectional"))
    )
    (net (code "180") (name "unconnected-(IC7-CBUS4-Pad12)") (class "Default")
      (node (ref "IC7") (pin "12") (pinfunction "CBUS4_12") (pintype "bidirectional"))
    )
    (net (code "181") (name "unconnected-(IC7-OSCI-Pad27)") (class "Default")
      (node (ref "IC7") (pin "27") (pinfunction "OSCI_27") (pintype "input"))
    )
    (net (code "182") (name "unconnected-(IC7-OSCO-Pad28)") (class "Default")
      (node (ref "IC7") (pin "28") (pinfunction "OSCO_28") (pintype "output"))
    )
    (net (code "183") (name "unconnected-(IC7-~{CTS}-Pad11)") (class "Default")
      (node (ref "IC7") (pin "11") (pinfunction "~{CTS}_11") (pintype "input"))
    )
    (net (code "184") (name "unconnected-(IC7-~{DCD}-Pad10)") (class "Default")
      (node (ref "IC7") (pin "10") (pinfunction "~{DCD}_10") (pintype "input"))
    )
    (net (code "185") (name "unconnected-(IC7-~{DSR}-Pad9)") (class "Default")
      (node (ref "IC7") (pin "9") (pinfunction "~{DSR}_9") (pintype "input"))
    )
    (net (code "186") (name "unconnected-(IC7-~{DTR}-Pad2)") (class "Default")
      (node (ref "IC7") (pin "2") (pinfunction "~{DTR}_2") (pintype "output"))
    )
    (net (code "187") (name "unconnected-(IC7-~{RI}-Pad6)") (class "Default")
      (node (ref "IC7") (pin "6") (pinfunction "~{RI}_6") (pintype "input"))
    )
    (net (code "188") (name "unconnected-(IC7-~{RTS}-Pad3)") (class "Default")
      (node (ref "IC7") (pin "3") (pinfunction "~{RTS}_3") (pintype "output"))
    )
    (net (code "189") (name "unconnected-(IC8-CLKIN-Pad31)") (class "Default")
      (node (ref "IC8") (pin "31") (pinfunction "CLKIN_31") (pintype "bidirectional"))
    )
    (net (code "190") (name "unconnected-(IC8-CLKSEL-Pad17)") (class "Default")
      (node (ref "IC8") (pin "17") (pinfunction "CLKSEL_17") (pintype "bidirectional"))
    )
    (net (code "191") (name "unconnected-(IC8-~{SHTDN}-Pad32)") (class "Default")
      (node (ref "IC8") (pin "32") (pinfunction "~{SHTDN}_32") (pintype "bidirectional"))
    )
  )
)
